# board1corrected.net
KiCad netlist of a schematic drawn in EAGLE
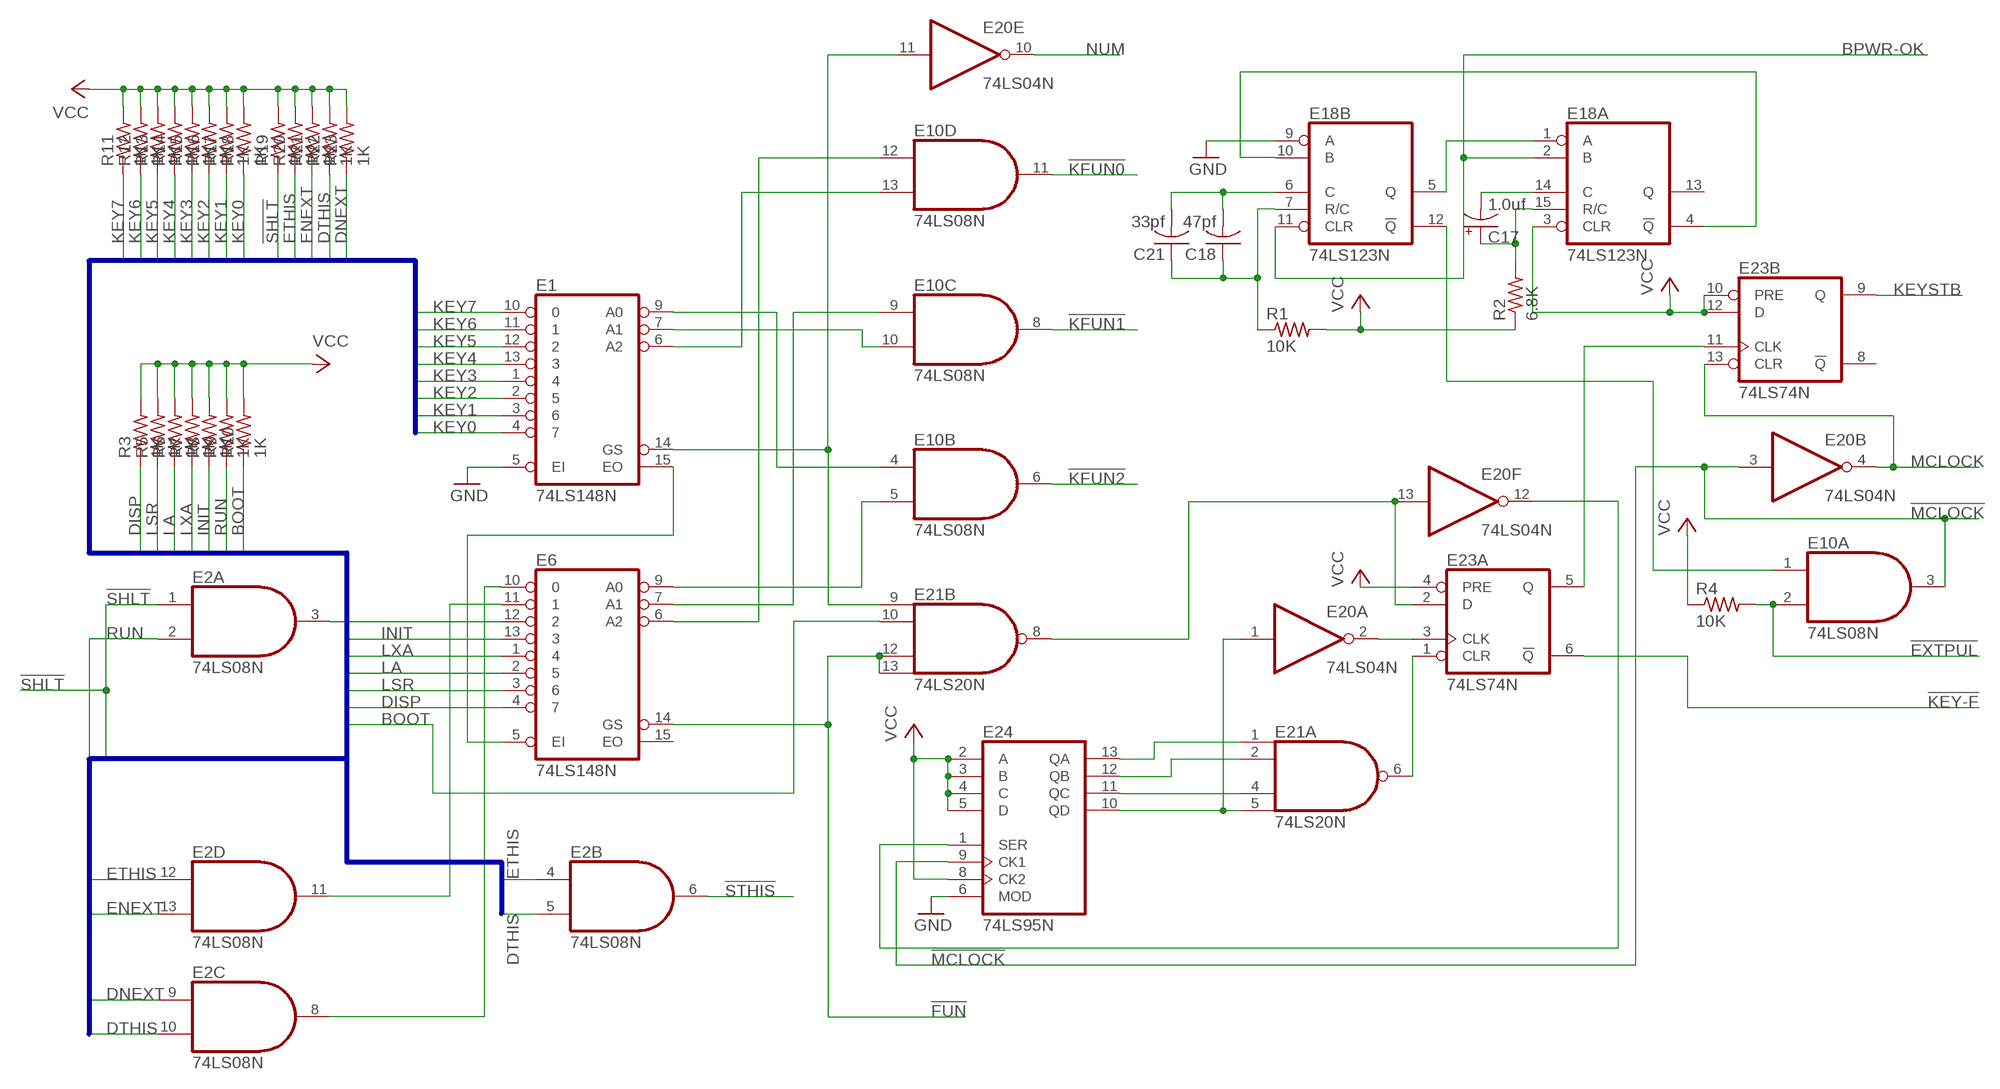
[diagram p0: schematic, sheet 1]
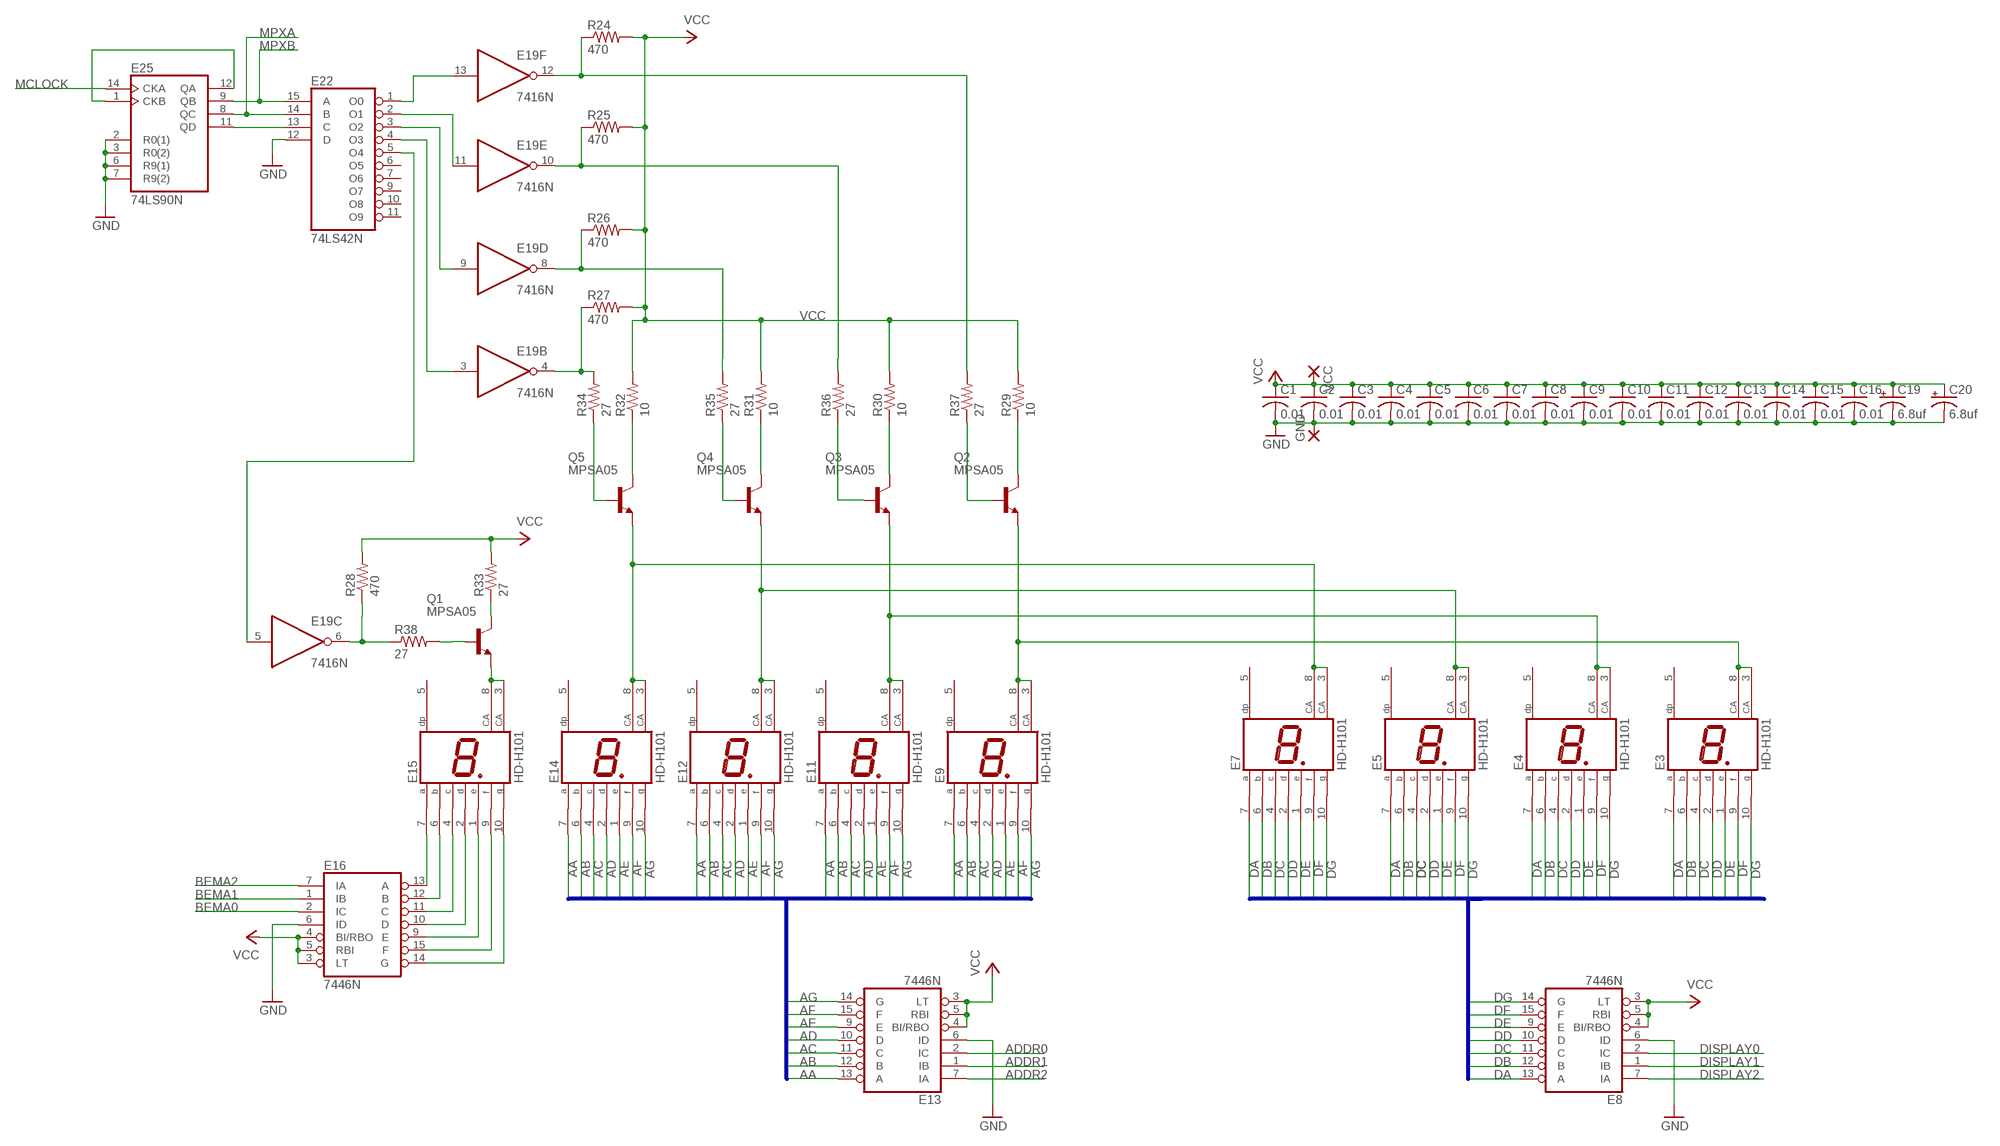
[diagram p1: schematic, sheet 2]
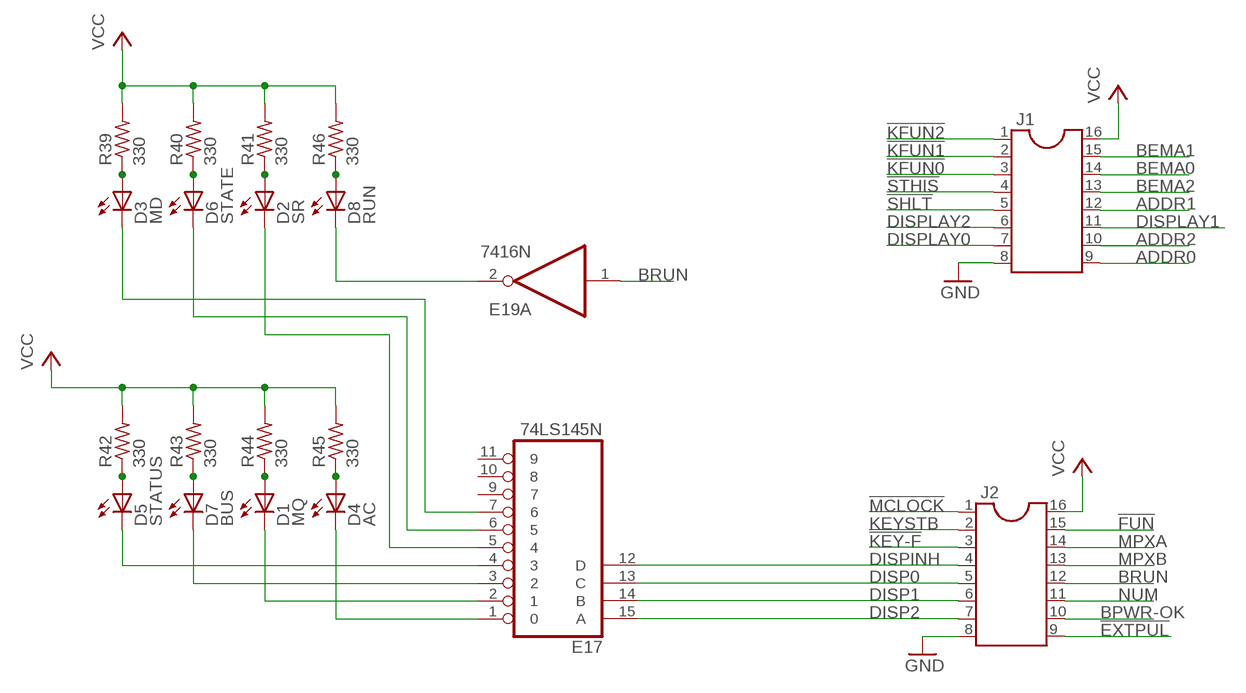
[diagram p2: schematic, sheet 3]
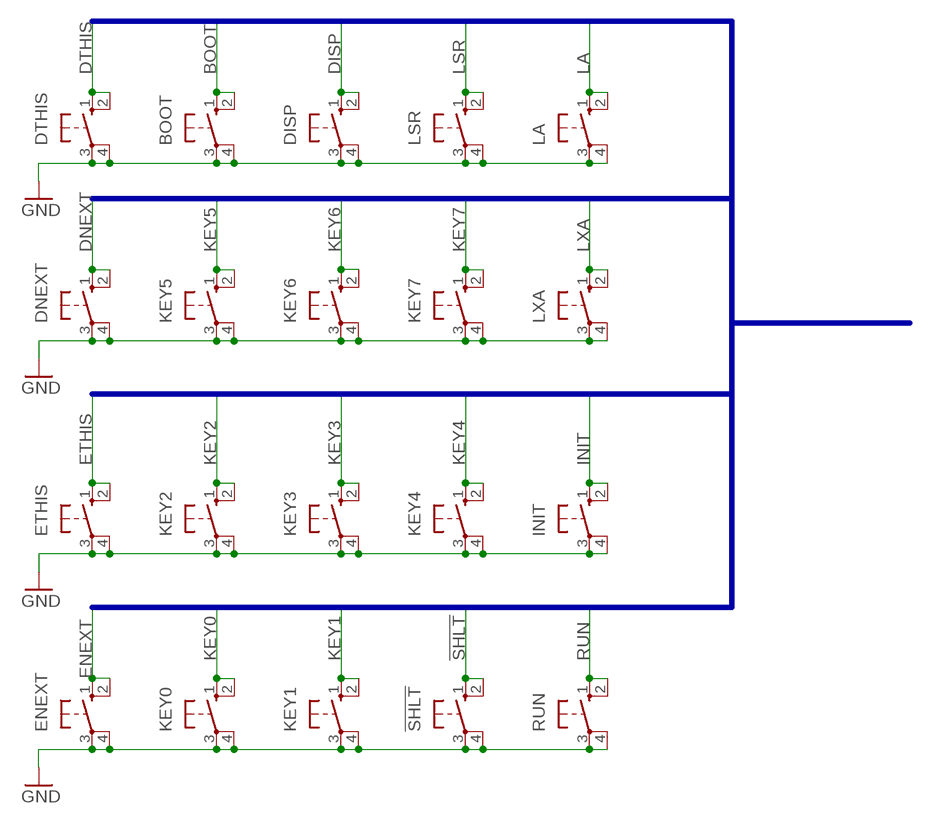
[diagram p3: schematic, sheet 4]

(export (version "E")
  (design (tool "Eeschema 10.0.6"))
  (components
    (comp (ref "C1")
      (value "0.01")
      (footprint "eagle-import:C050-025X075")
      (libsource (lib "eagle-import") (part "C-US050-025X075"))
    )
    (comp (ref "C2")
      (value "0.01")
      (footprint "eagle-import:C050-025X075")
      (libsource (lib "eagle-import") (part "C-US050-025X075"))
    )
    (comp (ref "C3")
      (value "0.01")
      (footprint "eagle-import:C050-025X075")
      (libsource (lib "eagle-import") (part "C-US050-025X075"))
    )
    (comp (ref "C4")
      (value "0.01")
      (footprint "eagle-import:C050-025X075")
      (libsource (lib "eagle-import") (part "C-US050-025X075"))
    )
    (comp (ref "C5")
      (value "0.01")
      (footprint "eagle-import:C050-025X075")
      (libsource (lib "eagle-import") (part "C-US050-025X075"))
    )
    (comp (ref "C6")
      (value "0.01")
      (footprint "eagle-import:C050-025X075")
      (libsource (lib "eagle-import") (part "C-US050-025X075"))
    )
    (comp (ref "C7")
      (value "0.01")
      (footprint "eagle-import:C050-025X075")
      (libsource (lib "eagle-import") (part "C-US050-025X075"))
    )
    (comp (ref "C8")
      (value "0.01")
      (footprint "eagle-import:C050-025X075")
      (libsource (lib "eagle-import") (part "C-US050-025X075"))
    )
    (comp (ref "C9")
      (value "0.01")
      (footprint "eagle-import:C050-025X075")
      (libsource (lib "eagle-import") (part "C-US050-025X075"))
    )
    (comp (ref "C10")
      (value "0.01")
      (footprint "eagle-import:C050-025X075")
      (libsource (lib "eagle-import") (part "C-US050-025X075"))
    )
    (comp (ref "C11")
      (value "0.01")
      (footprint "eagle-import:C050-025X075")
      (libsource (lib "eagle-import") (part "C-US050-025X075"))
    )
    (comp (ref "C12")
      (value "0.01")
      (footprint "eagle-import:C050-025X075")
      (libsource (lib "eagle-import") (part "C-US050-025X075"))
    )
    (comp (ref "C13")
      (value "0.01")
      (footprint "eagle-import:C050-025X075")
      (libsource (lib "eagle-import") (part "C-US050-025X075"))
    )
    (comp (ref "C14")
      (value "0.01")
      (footprint "eagle-import:C050-025X075")
      (libsource (lib "eagle-import") (part "C-US050-025X075"))
    )
    (comp (ref "C15")
      (value "0.01")
      (footprint "eagle-import:C050-025X075")
      (libsource (lib "eagle-import") (part "C-US050-025X075"))
    )
    (comp (ref "C16")
      (value "0.01")
      (footprint "eagle-import:C050-025X075")
      (libsource (lib "eagle-import") (part "C-US050-025X075"))
    )
    (comp (ref "C19")
      (value "6.8uf")
      (footprint "eagle-import:E22-6")
      (libsource (lib "eagle-import") (part "CPOL-USE22-6AXIAL"))
    )
    (comp (ref "C20")
      (value "6.8uf")
      (footprint "eagle-import:E22-6")
      (libsource (lib "eagle-import") (part "CPOL-USE22-6AXIAL"))
    )
    (comp (ref "E3")
      (value "HD-H101")
      (footprint "eagle-import:HDSP-M")
      (libsource (lib "eagle-import") (part "HD-H101"))
    )
    (comp (ref "E4")
      (value "HD-H101")
      (footprint "eagle-import:HDSP-M")
      (libsource (lib "eagle-import") (part "HD-H101"))
    )
    (comp (ref "E5")
      (value "HD-H101")
      (footprint "eagle-import:HDSP-M")
      (libsource (lib "eagle-import") (part "HD-H101"))
    )
    (comp (ref "E7")
      (value "HD-H101")
      (footprint "eagle-import:HDSP-M")
      (libsource (lib "eagle-import") (part "HD-H101"))
    )
    (comp (ref "E8")
      (value "7446N")
      (footprint "eagle-import:DIL16")
      (libsource (lib "eagle-import") (part "7446N"))
    )
    (comp (ref "E9")
      (value "HD-H101")
      (footprint "eagle-import:HDSP-M")
      (libsource (lib "eagle-import") (part "HD-H101"))
    )
    (comp (ref "E11")
      (value "HD-H101")
      (footprint "eagle-import:HDSP-M")
      (libsource (lib "eagle-import") (part "HD-H101"))
    )
    (comp (ref "E12")
      (value "HD-H101")
      (footprint "eagle-import:HDSP-M")
      (libsource (lib "eagle-import") (part "HD-H101"))
    )
    (comp (ref "E13")
      (value "7446N")
      (footprint "eagle-import:DIL16")
      (libsource (lib "eagle-import") (part "7446N"))
    )
    (comp (ref "E14")
      (value "HD-H101")
      (footprint "eagle-import:HDSP-M")
      (libsource (lib "eagle-import") (part "HD-H101"))
    )
    (comp (ref "E15")
      (value "HD-H101")
      (footprint "eagle-import:HDSP-M")
      (libsource (lib "eagle-import") (part "HD-H101"))
    )
    (comp (ref "E16")
      (value "7446N")
      (footprint "eagle-import:DIL16")
      (libsource (lib "eagle-import") (part "7446N"))
    )
    (comp (ref "E19")
      (value "7416N")
      (footprint "eagle-import:DIL14")
      (libsource (lib "eagle-import") (part "7416N"))
    )
    (comp (ref "E22")
      (value "74LS42N")
      (footprint "eagle-import:DIL16")
      (libsource (lib "eagle-import") (part "7442NLS"))
    )
    (comp (ref "E25")
      (value "74LS90N")
      (footprint "eagle-import:DIL14")
      (libsource (lib "eagle-import") (part "7490NLS"))
    )
    (comp (ref "GND")
      (value "3,81/1,4")
      (footprint "eagle-import:3,81_1,4")
      (libsource (lib "eagle-import") (part "3,81/1,4"))
    )
    (comp (ref "Q1")
      (value "MPSA05")
      (footprint "eagle-import:TO18")
      (libsource (lib "eagle-import") (part "2N2222A"))
    )
    (comp (ref "Q2")
      (value "MPSA05")
      (footprint "eagle-import:TO18")
      (libsource (lib "eagle-import") (part "2N2222A"))
    )
    (comp (ref "Q3")
      (value "MPSA05")
      (footprint "eagle-import:TO18")
      (libsource (lib "eagle-import") (part "2N2222A"))
    )
    (comp (ref "Q4")
      (value "MPSA05")
      (footprint "eagle-import:TO18")
      (libsource (lib "eagle-import") (part "2N2222A"))
    )
    (comp (ref "Q5")
      (value "MPSA05")
      (footprint "eagle-import:TO18")
      (libsource (lib "eagle-import") (part "2N2222A"))
    )
    (comp (ref "R24")
      (value "470")
      (footprint "eagle-import:0207_10")
      (libsource (lib "eagle-import") (part "R-US_0207/10"))
    )
    (comp (ref "R25")
      (value "470")
      (footprint "eagle-import:0207_10")
      (libsource (lib "eagle-import") (part "R-US_0207/10"))
    )
    (comp (ref "R26")
      (value "470")
      (footprint "eagle-import:0207_10")
      (libsource (lib "eagle-import") (part "R-US_0207/10"))
    )
    (comp (ref "R27")
      (value "470")
      (footprint "eagle-import:0207_10")
      (libsource (lib "eagle-import") (part "R-US_0207/10"))
    )
    (comp (ref "R28")
      (value "470")
      (footprint "eagle-import:0207_10")
      (libsource (lib "eagle-import") (part "R-US_0207/10"))
    )
    (comp (ref "R29")
      (value "10")
      (footprint "eagle-import:0207_10")
      (libsource (lib "eagle-import") (part "R-US_0207/10"))
    )
    (comp (ref "R30")
      (value "10")
      (footprint "eagle-import:0207_10")
      (libsource (lib "eagle-import") (part "R-US_0207/10"))
    )
    (comp (ref "R31")
      (value "10")
      (footprint "eagle-import:0207_10")
      (libsource (lib "eagle-import") (part "R-US_0207/10"))
    )
    (comp (ref "R32")
      (value "10")
      (footprint "eagle-import:0207_10")
      (libsource (lib "eagle-import") (part "R-US_0207/10"))
    )
    (comp (ref "R33")
      (value "27")
      (footprint "eagle-import:0207_10")
      (libsource (lib "eagle-import") (part "R-US_0207/10"))
    )
    (comp (ref "R34")
      (value "27")
      (footprint "eagle-import:0207_10")
      (libsource (lib "eagle-import") (part "R-US_0207/10"))
    )
    (comp (ref "R35")
      (value "27")
      (footprint "eagle-import:0207_10")
      (libsource (lib "eagle-import") (part "R-US_0207/10"))
    )
    (comp (ref "R36")
      (value "27")
      (footprint "eagle-import:0207_10")
      (libsource (lib "eagle-import") (part "R-US_0207/10"))
    )
    (comp (ref "R37")
      (value "27")
      (footprint "eagle-import:0207_10")
      (libsource (lib "eagle-import") (part "R-US_0207/10"))
    )
    (comp (ref "R38")
      (value "27")
      (footprint "eagle-import:0207_10")
      (libsource (lib "eagle-import") (part "R-US_0207/10"))
    )
    (comp (ref "VCC")
      (value "3,81/1,4")
      (footprint "eagle-import:3,81_1,4")
      (libsource (lib "eagle-import") (part "3,81/1,4"))
    )
    (comp (ref "C17")
      (value "1.0uf")
      (footprint "eagle-import:E15-5")
      (libsource (lib "eagle-import") (part "CPOL-USE15-5AXIAL"))
    )
    (comp (ref "C18")
      (value "47pf")
      (footprint "eagle-import:C050-025X075")
      (libsource (lib "eagle-import") (part "C-US050-025X075"))
    )
    (comp (ref "C21")
      (value "33pf")
      (footprint "eagle-import:C050-025X075")
      (libsource (lib "eagle-import") (part "C-US050-025X075"))
    )
    (comp (ref "E1")
      (value "74LS148N")
      (footprint "eagle-import:DIL16")
      (libsource (lib "eagle-import") (part "74148NLS"))
    )
    (comp (ref "E2")
      (value "74LS08N")
      (footprint "eagle-import:DIL14")
      (libsource (lib "eagle-import") (part "7408NLS"))
    )
    (comp (ref "E6")
      (value "74LS148N")
      (footprint "eagle-import:DIL16")
      (libsource (lib "eagle-import") (part "74148NLS"))
    )
    (comp (ref "E10")
      (value "74LS08N")
      (footprint "eagle-import:DIL14")
      (libsource (lib "eagle-import") (part "7408NLS"))
    )
    (comp (ref "E18")
      (value "74LS123N")
      (footprint "eagle-import:DIL16")
      (libsource (lib "eagle-import") (part "74123NLS"))
    )
    (comp (ref "E20")
      (value "74LS04N")
      (footprint "eagle-import:DIL14")
      (libsource (lib "eagle-import") (part "7404NLS"))
    )
    (comp (ref "E21")
      (value "74LS20N")
      (footprint "eagle-import:DIL14")
      (libsource (lib "eagle-import") (part "7420NLS"))
    )
    (comp (ref "E23")
      (value "74LS74N")
      (footprint "eagle-import:DIL14")
      (libsource (lib "eagle-import") (part "7474NLS"))
    )
    (comp (ref "E24")
      (value "74LS95N")
      (footprint "eagle-import:DIL14")
      (libsource (lib "eagle-import") (part "7495NLS"))
    )
    (comp (ref "R1")
      (value "10K")
      (footprint "eagle-import:0207_10")
      (libsource (lib "eagle-import") (part "R-US_0207/10"))
    )
    (comp (ref "R2")
      (value "6.8K")
      (footprint "eagle-import:0207_10")
      (libsource (lib "eagle-import") (part "R-US_0207/10"))
    )
    (comp (ref "R3")
      (value "1K")
      (footprint "eagle-import:0207_10")
      (libsource (lib "eagle-import") (part "R-US_0207/10"))
    )
    (comp (ref "R4")
      (value "10K")
      (footprint "eagle-import:0207_10")
      (libsource (lib "eagle-import") (part "R-US_0207/10"))
    )
    (comp (ref "R5")
      (value "1K")
      (footprint "eagle-import:0207_10")
      (libsource (lib "eagle-import") (part "R-US_0207/10"))
    )
    (comp (ref "R6")
      (value "1K")
      (footprint "eagle-import:0207_10")
      (libsource (lib "eagle-import") (part "R-US_0207/10"))
    )
    (comp (ref "R7")
      (value "1K")
      (footprint "eagle-import:0207_10")
      (libsource (lib "eagle-import") (part "R-US_0207/10"))
    )
    (comp (ref "R8")
      (value "1K")
      (footprint "eagle-import:0207_10")
      (libsource (lib "eagle-import") (part "R-US_0207/10"))
    )
    (comp (ref "R9")
      (value "1K")
      (footprint "eagle-import:0207_10")
      (libsource (lib "eagle-import") (part "R-US_0207/10"))
    )
    (comp (ref "R10")
      (value "1K")
      (footprint "eagle-import:0207_10")
      (libsource (lib "eagle-import") (part "R-US_0207/10"))
    )
    (comp (ref "R11")
      (value "1K")
      (footprint "eagle-import:0207_10")
      (libsource (lib "eagle-import") (part "R-US_0207/10"))
    )
    (comp (ref "R12")
      (value "1K")
      (footprint "eagle-import:0207_10")
      (libsource (lib "eagle-import") (part "R-US_0207/10"))
    )
    (comp (ref "R13")
      (value "1K")
      (footprint "eagle-import:0207_10")
      (libsource (lib "eagle-import") (part "R-US_0207/10"))
    )
    (comp (ref "R14")
      (value "1K")
      (footprint "eagle-import:0207_10")
      (libsource (lib "eagle-import") (part "R-US_0207/10"))
    )
    (comp (ref "R15")
      (value "1K")
      (footprint "eagle-import:0207_10")
      (libsource (lib "eagle-import") (part "R-US_0207/10"))
    )
    (comp (ref "R16")
      (value "1K")
      (footprint "eagle-import:0207_10")
      (libsource (lib "eagle-import") (part "R-US_0207/10"))
    )
    (comp (ref "R17")
      (value "1K")
      (footprint "eagle-import:0207_10")
      (libsource (lib "eagle-import") (part "R-US_0207/10"))
    )
    (comp (ref "R18")
      (value "1K")
      (footprint "eagle-import:0207_10")
      (libsource (lib "eagle-import") (part "R-US_0207/10"))
    )
    (comp (ref "R19")
      (value "1K")
      (footprint "eagle-import:0207_10")
      (libsource (lib "eagle-import") (part "R-US_0207/10"))
    )
    (comp (ref "R20")
      (value "1K")
      (footprint "eagle-import:0207_10")
      (libsource (lib "eagle-import") (part "R-US_0207/10"))
    )
    (comp (ref "R21")
      (value "1K")
      (footprint "eagle-import:0207_10")
      (libsource (lib "eagle-import") (part "R-US_0207/10"))
    )
    (comp (ref "R22")
      (value "1K")
      (footprint "eagle-import:0207_10")
      (libsource (lib "eagle-import") (part "R-US_0207/10"))
    )
    (comp (ref "R23")
      (value "1K")
      (footprint "eagle-import:0207_10")
      (libsource (lib "eagle-import") (part "R-US_0207/10"))
    )
    (comp (ref "D1")
      (value "MQ")
      (footprint "eagle-import:LED5MM")
      (libsource (lib "eagle-import") (part "LED5MM"))
    )
    (comp (ref "D2")
      (value "SR")
      (footprint "eagle-import:LED5MM")
      (libsource (lib "eagle-import") (part "LED5MM"))
    )
    (comp (ref "D3")
      (value "MD")
      (footprint "eagle-import:LED5MM")
      (libsource (lib "eagle-import") (part "LED5MM"))
    )
    (comp (ref "D4")
      (value "AC")
      (footprint "eagle-import:LED5MM")
      (libsource (lib "eagle-import") (part "LED5MM"))
    )
    (comp (ref "D5")
      (value "STATUS")
      (footprint "eagle-import:LED5MM")
      (libsource (lib "eagle-import") (part "LED5MM"))
    )
    (comp (ref "D6")
      (value "STATE")
      (footprint "eagle-import:LED5MM")
      (libsource (lib "eagle-import") (part "LED5MM"))
    )
    (comp (ref "D7")
      (value "BUS")
      (footprint "eagle-import:LED5MM")
      (libsource (lib "eagle-import") (part "LED5MM"))
    )
    (comp (ref "D8")
      (value "RUN")
      (footprint "eagle-import:LED5MM")
      (libsource (lib "eagle-import") (part "LED5MM"))
    )
    (comp (ref "E17")
      (value "74LS145N")
      (footprint "eagle-import:DIL16")
      (libsource (lib "eagle-import") (part "74145NLS"))
    )
    (comp (ref "J1")
      (value "DIL16S")
      (footprint "eagle-import:SOCKET-16")
      (libsource (lib "eagle-import") (part "DIL16S"))
    )
    (comp (ref "J2")
      (value "DIL16S")
      (footprint "eagle-import:SOCKET-16")
      (libsource (lib "eagle-import") (part "DIL16S"))
    )
    (comp (ref "R39")
      (value "330")
      (footprint "eagle-import:0207_10")
      (libsource (lib "eagle-import") (part "R-US_0207/10"))
    )
    (comp (ref "R40")
      (value "330")
      (footprint "eagle-import:0207_10")
      (libsource (lib "eagle-import") (part "R-US_0207/10"))
    )
    (comp (ref "R41")
      (value "330")
      (footprint "eagle-import:0207_10")
      (libsource (lib "eagle-import") (part "R-US_0207/10"))
    )
    (comp (ref "R42")
      (value "330")
      (footprint "eagle-import:0207_10")
      (libsource (lib "eagle-import") (part "R-US_0207/10"))
    )
    (comp (ref "R43")
      (value "330")
      (footprint "eagle-import:0207_10")
      (libsource (lib "eagle-import") (part "R-US_0207/10"))
    )
    (comp (ref "R44")
      (value "330")
      (footprint "eagle-import:0207_10")
      (libsource (lib "eagle-import") (part "R-US_0207/10"))
    )
    (comp (ref "R45")
      (value "330")
      (footprint "eagle-import:0207_10")
      (libsource (lib "eagle-import") (part "R-US_0207/10"))
    )
    (comp (ref "R46")
      (value "330")
      (footprint "eagle-import:0207_10")
      (libsource (lib "eagle-import") (part "R-US_0207/10"))
    )
    (comp (ref "!SHLT")
      (value "40-XX")
      (footprint "eagle-import:B3F-40XX")
      (fields (field (name "MF") "OMRON COMPONENTS USA") (field (name "MPN") "B3F-4000"))
      (libsource (lib "eagle-import") (part "40-XX"))
    )
    (comp (ref "BOOT")
      (value "40-XX")
      (footprint "eagle-import:B3F-40XX")
      (fields (field (name "MF") "OMRON COMPONENTS USA") (field (name "MPN") "B3F-4000"))
      (libsource (lib "eagle-import") (part "40-XX"))
    )
    (comp (ref "DISP")
      (value "40-XX")
      (footprint "eagle-import:B3F-40XX")
      (fields (field (name "MF") "OMRON COMPONENTS USA") (field (name "MPN") "B3F-4000"))
      (libsource (lib "eagle-import") (part "40-XX"))
    )
    (comp (ref "DNEXT")
      (value "40-XX")
      (footprint "eagle-import:B3F-40XX")
      (fields (field (name "MF") "OMRON COMPONENTS USA") (field (name "MPN") "B3F-4000"))
      (libsource (lib "eagle-import") (part "40-XX"))
    )
    (comp (ref "DTHIS")
      (value "40-XX")
      (footprint "eagle-import:B3F-40XX")
      (fields (field (name "MF") "OMRON COMPONENTS USA") (field (name "MPN") "B3F-4000"))
      (libsource (lib "eagle-import") (part "40-XX"))
    )
    (comp (ref "ENEXT")
      (value "40-XX")
      (footprint "eagle-import:B3F-40XX")
      (fields (field (name "MF") "OMRON COMPONENTS USA") (field (name "MPN") "B3F-4000"))
      (libsource (lib "eagle-import") (part "40-XX"))
    )
    (comp (ref "ETHIS")
      (value "40-XX")
      (footprint "eagle-import:B3F-40XX")
      (fields (field (name "MF") "OMRON COMPONENTS USA") (field (name "MPN") "B3F-4000"))
      (libsource (lib "eagle-import") (part "40-XX"))
    )
    (comp (ref "INIT")
      (value "40-XX")
      (footprint "eagle-import:B3F-40XX")
      (fields (field (name "MF") "OMRON COMPONENTS USA") (field (name "MPN") "B3F-4000"))
      (libsource (lib "eagle-import") (part "40-XX"))
    )
    (comp (ref "KEY0")
      (value "40-XX")
      (footprint "eagle-import:B3F-40XX")
      (fields (field (name "MF") "OMRON COMPONENTS USA") (field (name "MPN") "B3F-4000"))
      (libsource (lib "eagle-import") (part "40-XX"))
    )
    (comp (ref "KEY1")
      (value "40-XX")
      (footprint "eagle-import:B3F-40XX")
      (fields (field (name "MF") "OMRON COMPONENTS USA") (field (name "MPN") "B3F-4000"))
      (libsource (lib "eagle-import") (part "40-XX"))
    )
    (comp (ref "KEY2")
      (value "40-XX")
      (footprint "eagle-import:B3F-40XX")
      (fields (field (name "MF") "OMRON COMPONENTS USA") (field (name "MPN") "B3F-4000"))
      (libsource (lib "eagle-import") (part "40-XX"))
    )
    (comp (ref "KEY3")
      (value "40-XX")
      (footprint "eagle-import:B3F-40XX")
      (fields (field (name "MF") "OMRON COMPONENTS USA") (field (name "MPN") "B3F-4000"))
      (libsource (lib "eagle-import") (part "40-XX"))
    )
    (comp (ref "KEY4")
      (value "40-XX")
      (footprint "eagle-import:B3F-40XX")
      (fields (field (name "MF") "OMRON COMPONENTS USA") (field (name "MPN") "B3F-4000"))
      (libsource (lib "eagle-import") (part "40-XX"))
    )
    (comp (ref "KEY5")
      (value "40-XX")
      (footprint "eagle-import:B3F-40XX")
      (fields (field (name "MF") "OMRON COMPONENTS USA") (field (name "MPN") "B3F-4000"))
      (libsource (lib "eagle-import") (part "40-XX"))
    )
    (comp (ref "KEY6")
      (value "40-XX")
      (footprint "eagle-import:B3F-40XX")
      (fields (field (name "MF") "OMRON COMPONENTS USA") (field (name "MPN") "B3F-4000"))
      (libsource (lib "eagle-import") (part "40-XX"))
    )
    (comp (ref "KEY7")
      (value "40-XX")
      (footprint "eagle-import:B3F-40XX")
      (fields (field (name "MF") "OMRON COMPONENTS USA") (field (name "MPN") "B3F-4000"))
      (libsource (lib "eagle-import") (part "40-XX"))
    )
    (comp (ref "LA")
      (value "40-XX")
      (footprint "eagle-import:B3F-40XX")
      (fields (field (name "MF") "OMRON COMPONENTS USA") (field (name "MPN") "B3F-4000"))
      (libsource (lib "eagle-import") (part "40-XX"))
    )
    (comp (ref "LSR")
      (value "40-XX")
      (footprint "eagle-import:B3F-40XX")
      (fields (field (name "MF") "OMRON COMPONENTS USA") (field (name "MPN") "B3F-4000"))
      (libsource (lib "eagle-import") (part "40-XX"))
    )
    (comp (ref "LXA")
      (value "40-XX")
      (footprint "eagle-import:B3F-40XX")
      (fields (field (name "MF") "OMRON COMPONENTS USA") (field (name "MPN") "B3F-4000"))
      (libsource (lib "eagle-import") (part "40-XX"))
    )
    (comp (ref "RUN")
      (value "40-XX")
      (footprint "eagle-import:B3F-40XX")
      (fields (field (name "MF") "OMRON COMPONENTS USA") (field (name "MPN") "B3F-4000"))
      (libsource (lib "eagle-import") (part "40-XX"))
    )
  )
  (nets
    (net (code "1") (name "AA") (class "Default")
      (node (ref "E11") (pin "7") (pinfunction "A_7") (pintype "passive"))
      (node (ref "E12") (pin "7") (pinfunction "A_7") (pintype "passive"))
      (node (ref "E13") (pin "13") (pinfunction "A_13") (pintype "open_collector"))
      (node (ref "E14") (pin "7") (pinfunction "A_7") (pintype "passive"))
      (node (ref "E9") (pin "7") (pinfunction "A_7") (pintype "passive"))
    )
    (net (code "2") (name "AB") (class "Default")
      (node (ref "E11") (pin "6") (pinfunction "B_6") (pintype "passive"))
      (node (ref "E12") (pin "6") (pinfunction "B_6") (pintype "passive"))
      (node (ref "E13") (pin "12") (pinfunction "B_12") (pintype "open_collector"))
      (node (ref "E14") (pin "6") (pinfunction "B_6") (pintype "passive"))
      (node (ref "E9") (pin "6") (pinfunction "B_6") (pintype "passive"))
    )
    (net (code "3") (name "AC") (class "Default")
      (node (ref "E11") (pin "4") (pinfunction "C_4") (pintype "passive"))
      (node (ref "E12") (pin "4") (pinfunction "C_4") (pintype "passive"))
      (node (ref "E13") (pin "11") (pinfunction "C_11") (pintype "open_collector"))
      (node (ref "E14") (pin "4") (pinfunction "C_4") (pintype "passive"))
      (node (ref "E9") (pin "4") (pinfunction "C_4") (pintype "passive"))
    )
    (net (code "4") (name "AD") (class "Default")
      (node (ref "E11") (pin "2") (pinfunction "D_2") (pintype "passive"))
      (node (ref "E12") (pin "2") (pinfunction "D_2") (pintype "passive"))
      (node (ref "E13") (pin "10") (pinfunction "D_10") (pintype "open_collector"))
      (node (ref "E14") (pin "2") (pinfunction "D_2") (pintype "passive"))
      (node (ref "E9") (pin "2") (pinfunction "D_2") (pintype "passive"))
    )
    (net (code "5") (name "ADDR0") (class "Default")
      (node (ref "E13") (pin "2") (pinfunction "IC_2") (pintype "input"))
      (node (ref "J1") (pin "9") (pinfunction "9_9") (pintype "passive"))
    )
    (net (code "6") (name "ADDR1") (class "Default")
      (node (ref "E13") (pin "1") (pinfunction "IB_1") (pintype "input"))
      (node (ref "J1") (pin "12") (pinfunction "12_12") (pintype "passive"))
    )
    (net (code "7") (name "ADDR2") (class "Default")
      (node (ref "E13") (pin "7") (pinfunction "IA_7") (pintype "input"))
      (node (ref "J1") (pin "10") (pinfunction "10_10") (pintype "passive"))
    )
    (net (code "8") (name "AE") (class "Default")
      (node (ref "E11") (pin "1") (pinfunction "E_1") (pintype "passive"))
      (node (ref "E12") (pin "1") (pinfunction "E_1") (pintype "passive"))
      (node (ref "E13") (pin "9") (pinfunction "E_9") (pintype "open_collector"))
      (node (ref "E14") (pin "1") (pinfunction "E_1") (pintype "passive"))
      (node (ref "E9") (pin "1") (pinfunction "E_1") (pintype "passive"))
    )
    (net (code "9") (name "AF") (class "Default")
      (node (ref "E11") (pin "9") (pinfunction "F_9") (pintype "passive"))
      (node (ref "E12") (pin "9") (pinfunction "F_9") (pintype "passive"))
      (node (ref "E13") (pin "15") (pinfunction "F_15") (pintype "open_collector"))
      (node (ref "E14") (pin "9") (pinfunction "F_9") (pintype "passive"))
      (node (ref "E9") (pin "9") (pinfunction "F_9") (pintype "passive"))
    )
    (net (code "10") (name "AG") (class "Default")
      (node (ref "E11") (pin "10") (pinfunction "G_10") (pintype "passive"))
      (node (ref "E12") (pin "10") (pinfunction "G_10") (pintype "passive"))
      (node (ref "E13") (pin "14") (pinfunction "G_14") (pintype "open_collector"))
      (node (ref "E14") (pin "10") (pinfunction "G_10") (pintype "passive"))
      (node (ref "E9") (pin "10") (pinfunction "G_10") (pintype "passive"))
    )
    (net (code "11") (name "BEMA0") (class "Default")
      (node (ref "E16") (pin "2") (pinfunction "IC_2") (pintype "input"))
      (node (ref "J1") (pin "14") (pinfunction "14_14") (pintype "passive"))
    )
    (net (code "12") (name "BEMA1") (class "Default")
      (node (ref "E16") (pin "1") (pinfunction "IB_1") (pintype "input"))
      (node (ref "J1") (pin "15") (pinfunction "15_15") (pintype "passive"))
    )
    (net (code "13") (name "BEMA2") (class "Default")
      (node (ref "E16") (pin "7") (pinfunction "IA_7") (pintype "input"))
      (node (ref "J1") (pin "13") (pinfunction "13_13") (pintype "passive"))
    )
    (net (code "14") (name "BOOT") (class "Default")
      (node (ref "BOOT") (pin "1") (pinfunction "S_1") (pintype "passive"))
      (node (ref "BOOT") (pin "2") (pinfunction "S1_2") (pintype "passive"))
      (node (ref "E21") (pin "10") (pinfunction "I1_10") (pintype "input"))
      (node (ref "R10") (pin "1") (pinfunction "1_1") (pintype "passive"))
    )
    (net (code "15") (name "BPWR-OK") (class "Default")
      (node (ref "E18") (pin "11") (pinfunction "CLR_11") (pintype "input"))
      (node (ref "E18") (pin "2") (pinfunction "B_2") (pintype "input"))
      (node (ref "J2") (pin "10") (pinfunction "10_10") (pintype "passive"))
    )
    (net (code "16") (name "BRUN") (class "Default")
      (node (ref "E19") (pin "1") (pinfunction "I_1") (pintype "input"))
      (node (ref "J2") (pin "12") (pinfunction "12_12") (pintype "passive"))
    )
    (net (code "17") (name "DA") (class "Default")
      (node (ref "E3") (pin "7") (pinfunction "A_7") (pintype "passive"))
      (node (ref "E4") (pin "7") (pinfunction "A_7") (pintype "passive"))
      (node (ref "E5") (pin "7") (pinfunction "A_7") (pintype "passive"))
      (node (ref "E7") (pin "7") (pinfunction "A_7") (pintype "passive"))
      (node (ref "E8") (pin "13") (pinfunction "A_13") (pintype "open_collector"))
    )
    (net (code "18") (name "DB") (class "Default")
      (node (ref "E3") (pin "6") (pinfunction "B_6") (pintype "passive"))
      (node (ref "E4") (pin "6") (pinfunction "B_6") (pintype "passive"))
      (node (ref "E5") (pin "6") (pinfunction "B_6") (pintype "passive"))
      (node (ref "E7") (pin "6") (pinfunction "B_6") (pintype "passive"))
      (node (ref "E8") (pin "12") (pinfunction "B_12") (pintype "open_collector"))
    )
    (net (code "19") (name "DC") (class "Default")
      (node (ref "E3") (pin "4") (pinfunction "C_4") (pintype "passive"))
      (node (ref "E4") (pin "4") (pinfunction "C_4") (pintype "passive"))
      (node (ref "E5") (pin "4") (pinfunction "C_4") (pintype "passive"))
      (node (ref "E7") (pin "4") (pinfunction "C_4") (pintype "passive"))
      (node (ref "E8") (pin "11") (pinfunction "C_11") (pintype "open_collector"))
    )
    (net (code "20") (name "DD") (class "Default")
      (node (ref "E3") (pin "2") (pinfunction "D_2") (pintype "passive"))
      (node (ref "E4") (pin "2") (pinfunction "D_2") (pintype "passive"))
      (node (ref "E5") (pin "2") (pinfunction "D_2") (pintype "passive"))
      (node (ref "E7") (pin "2") (pinfunction "D_2") (pintype "passive"))
      (node (ref "E8") (pin "10") (pinfunction "D_10") (pintype "open_collector"))
    )
    (net (code "21") (name "DE") (class "Default")
      (node (ref "E3") (pin "1") (pinfunction "E_1") (pintype "passive"))
      (node (ref "E4") (pin "1") (pinfunction "E_1") (pintype "passive"))
      (node (ref "E5") (pin "1") (pinfunction "E_1") (pintype "passive"))
      (node (ref "E7") (pin "1") (pinfunction "E_1") (pintype "passive"))
      (node (ref "E8") (pin "9") (pinfunction "E_9") (pintype "open_collector"))
    )
    (net (code "22") (name "DF") (class "Default")
      (node (ref "E3") (pin "9") (pinfunction "F_9") (pintype "passive"))
      (node (ref "E4") (pin "9") (pinfunction "F_9") (pintype "passive"))
      (node (ref "E5") (pin "9") (pinfunction "F_9") (pintype "passive"))
      (node (ref "E7") (pin "9") (pinfunction "F_9") (pintype "passive"))
      (node (ref "E8") (pin "15") (pinfunction "F_15") (pintype "open_collector"))
    )
    (net (code "23") (name "DG") (class "Default")
      (node (ref "E3") (pin "10") (pinfunction "G_10") (pintype "passive"))
      (node (ref "E4") (pin "10") (pinfunction "G_10") (pintype "passive"))
      (node (ref "E5") (pin "10") (pinfunction "G_10") (pintype "passive"))
      (node (ref "E7") (pin "10") (pinfunction "G_10") (pintype "passive"))
      (node (ref "E8") (pin "14") (pinfunction "G_14") (pintype "open_collector"))
    )
    (net (code "24") (name "DISP") (class "Default")
      (node (ref "DISP") (pin "1") (pinfunction "S_1") (pintype "passive"))
      (node (ref "DISP") (pin "2") (pinfunction "S1_2") (pintype "passive"))
      (node (ref "E6") (pin "4") (pinfunction "7_4") (pintype "input"))
      (node (ref "R3") (pin "1") (pinfunction "1_1") (pintype "passive"))
    )
    (net (code "25") (name "DISP0") (class "Default")
      (node (ref "E17") (pin "13") (pinfunction "C_13") (pintype "input"))
      (node (ref "J2") (pin "5") (pinfunction "5_5") (pintype "passive"))
    )
    (net (code "26") (name "DISP1") (class "Default")
      (node (ref "E17") (pin "14") (pinfunction "B_14") (pintype "input"))
      (node (ref "J2") (pin "6") (pinfunction "6_6") (pintype "passive"))
    )
    (net (code "27") (name "DISP2") (class "Default")
      (node (ref "E17") (pin "15") (pinfunction "A_15") (pintype "input"))
      (node (ref "J2") (pin "7") (pinfunction "7_7") (pintype "passive"))
    )
    (net (code "28") (name "DISPINH") (class "Default")
      (node (ref "E17") (pin "12") (pinfunction "D_12") (pintype "input"))
      (node (ref "J2") (pin "4") (pinfunction "4_4") (pintype "passive"))
    )
    (net (code "29") (name "DISPLAY0") (class "Default")
      (node (ref "E8") (pin "2") (pinfunction "IC_2") (pintype "input"))
      (node (ref "J1") (pin "7") (pinfunction "7_7") (pintype "passive"))
    )
    (net (code "30") (name "DISPLAY1") (class "Default")
      (node (ref "E8") (pin "1") (pinfunction "IB_1") (pintype "input"))
      (node (ref "J1") (pin "11") (pinfunction "11_11") (pintype "passive"))
    )
    (net (code "31") (name "DISPLAY2") (class "Default")
      (node (ref "E8") (pin "7") (pinfunction "IA_7") (pintype "input"))
      (node (ref "J1") (pin "6") (pinfunction "6_6") (pintype "passive"))
    )
    (net (code "32") (name "DNEXT") (class "Default")
      (node (ref "DNEXT") (pin "1") (pinfunction "S_1") (pintype "passive"))
      (node (ref "DNEXT") (pin "2") (pinfunction "S1_2") (pintype "passive"))
      (node (ref "E2") (pin "9") (pinfunction "I0_9") (pintype "input"))
      (node (ref "R23") (pin "1") (pinfunction "1_1") (pintype "passive"))
    )
    (net (code "33") (name "DTHIS") (class "Default")
      (node (ref "DTHIS") (pin "1") (pinfunction "S_1") (pintype "passive"))
      (node (ref "DTHIS") (pin "2") (pinfunction "S1_2") (pintype "passive"))
      (node (ref "E2") (pin "10") (pinfunction "I1_10") (pintype "input"))
      (node (ref "E2") (pin "5") (pinfunction "I1_5") (pintype "input"))
      (node (ref "R22") (pin "1") (pinfunction "1_1") (pintype "passive"))
    )
    (net (code "34") (name "ENEXT") (class "Default")
      (node (ref "E2") (pin "13") (pinfunction "I1_13") (pintype "input"))
      (node (ref "ENEXT") (pin "1") (pinfunction "S_1") (pintype "passive"))
      (node (ref "ENEXT") (pin "2") (pinfunction "S1_2") (pintype "passive"))
      (node (ref "R21") (pin "1") (pinfunction "1_1") (pintype "passive"))
    )
    (net (code "35") (name "ETHIS") (class "Default")
      (node (ref "E2") (pin "12") (pinfunction "I0_12") (pintype "input"))
      (node (ref "E2") (pin "4") (pinfunction "I0_4") (pintype "input"))
      (node (ref "ETHIS") (pin "1") (pinfunction "S_1") (pintype "passive"))
      (node (ref "ETHIS") (pin "2") (pinfunction "S1_2") (pintype "passive"))
      (node (ref "R20") (pin "1") (pinfunction "1_1") (pintype "passive"))
    )
    (net (code "36") (name "GND") (class "Default")
      (node (ref "!SHLT") (pin "3") (pinfunction "P_3") (pintype "passive"))
      (node (ref "!SHLT") (pin "4") (pinfunction "P1_4") (pintype "passive"))
      (node (ref "BOOT") (pin "3") (pinfunction "P_3") (pintype "passive"))
      (node (ref "BOOT") (pin "4") (pinfunction "P1_4") (pintype "passive"))
      (node (ref "C1") (pin "2") (pinfunction "2_2") (pintype "passive"))
      (node (ref "C10") (pin "2") (pinfunction "2_2") (pintype "passive"))
      (node (ref "C11") (pin "2") (pinfunction "2_2") (pintype "passive"))
      (node (ref "C12") (pin "2") (pinfunction "2_2") (pintype "passive"))
      (node (ref "C13") (pin "2") (pinfunction "2_2") (pintype "passive"))
      (node (ref "C14") (pin "2") (pinfunction "2_2") (pintype "passive"))
      (node (ref "C15") (pin "2") (pinfunction "2_2") (pintype "passive"))
      (node (ref "C16") (pin "2") (pinfunction "2_2") (pintype "passive"))
      (node (ref "C19") (pin "-") (pinfunction "-_-") (pintype "passive"))
      (node (ref "C2") (pin "2") (pinfunction "2_2") (pintype "passive"))
      (node (ref "C20") (pin "-") (pinfunction "-_-") (pintype "passive"))
      (node (ref "C3") (pin "2") (pinfunction "2_2") (pintype "passive"))
      (node (ref "C4") (pin "2") (pinfunction "2_2") (pintype "passive"))
      (node (ref "C5") (pin "2") (pinfunction "2_2") (pintype "passive"))
      (node (ref "C6") (pin "2") (pinfunction "2_2") (pintype "passive"))
      (node (ref "C7") (pin "2") (pinfunction "2_2") (pintype "passive"))
      (node (ref "C8") (pin "2") (pinfunction "2_2") (pintype "passive"))
      (node (ref "C9") (pin "2") (pinfunction "2_2") (pintype "passive"))
      (node (ref "DISP") (pin "3") (pinfunction "P_3") (pintype "passive"))
      (node (ref "DISP") (pin "4") (pinfunction "P1_4") (pintype "passive"))
      (node (ref "DNEXT") (pin "3") (pinfunction "P_3") (pintype "passive"))
      (node (ref "DNEXT") (pin "4") (pinfunction "P1_4") (pintype "passive"))
      (node (ref "DTHIS") (pin "3") (pinfunction "P_3") (pintype "passive"))
      (node (ref "DTHIS") (pin "4") (pinfunction "P1_4") (pintype "passive"))
      (node (ref "E1") (pin "5") (pinfunction "EI_5") (pintype "input"))
      (node (ref "E13") (pin "6") (pinfunction "ID_6") (pintype "input"))
      (node (ref "E16") (pin "6") (pinfunction "ID_6") (pintype "input"))
      (node (ref "E18") (pin "9") (pinfunction "A_9") (pintype "input"))
      (node (ref "E22") (pin "12") (pinfunction "D_12") (pintype "input"))
      (node (ref "E24") (pin "6") (pinfunction "MOD_6") (pintype "input"))
      (node (ref "E25") (pin "2") (pinfunction "R0(1)_2") (pintype "input"))
      (node (ref "E25") (pin "3") (pinfunction "R0(2)_3") (pintype "input"))
      (node (ref "E25") (pin "6") (pinfunction "R9(1)_6") (pintype "input"))
      (node (ref "E25") (pin "7") (pinfunction "R9(2)_7") (pintype "input"))
      (node (ref "E8") (pin "6") (pinfunction "ID_6") (pintype "input"))
      (node (ref "ENEXT") (pin "3") (pinfunction "P_3") (pintype "passive"))
      (node (ref "ENEXT") (pin "4") (pinfunction "P1_4") (pintype "passive"))
      (node (ref "ETHIS") (pin "3") (pinfunction "P_3") (pintype "passive"))
      (node (ref "ETHIS") (pin "4") (pinfunction "P1_4") (pintype "passive"))
      (node (ref "GND") (pin "1") (pinfunction "P_1") (pintype "passive"))
      (node (ref "INIT") (pin "3") (pinfunction "P_3") (pintype "passive"))
      (node (ref "INIT") (pin "4") (pinfunction "P1_4") (pintype "passive"))
      (node (ref "J1") (pin "8") (pinfunction "8_8") (pintype "passive"))
      (node (ref "J2") (pin "8") (pinfunction "8_8") (pintype "passive"))
      (node (ref "KEY0") (pin "3") (pinfunction "P_3") (pintype "passive"))
      (node (ref "KEY0") (pin "4") (pinfunction "P1_4") (pintype "passive"))
      (node (ref "KEY1") (pin "3") (pinfunction "P_3") (pintype "passive"))
      (node (ref "KEY1") (pin "4") (pinfunction "P1_4") (pintype "passive"))
      (node (ref "KEY2") (pin "3") (pinfunction "P_3") (pintype "passive"))
      (node (ref "KEY2") (pin "4") (pinfunction "P1_4") (pintype "passive"))
      (node (ref "KEY3") (pin "3") (pinfunction "P_3") (pintype "passive"))
      (node (ref "KEY3") (pin "4") (pinfunction "P1_4") (pintype "passive"))
      (node (ref "KEY4") (pin "3") (pinfunction "P_3") (pintype "passive"))
      (node (ref "KEY4") (pin "4") (pinfunction "P1_4") (pintype "passive"))
      (node (ref "KEY5") (pin "3") (pinfunction "P_3") (pintype "passive"))
      (node (ref "KEY5") (pin "4") (pinfunction "P1_4") (pintype "passive"))
      (node (ref "KEY6") (pin "3") (pinfunction "P_3") (pintype "passive"))
      (node (ref "KEY6") (pin "4") (pinfunction "P1_4") (pintype "passive"))
      (node (ref "KEY7") (pin "3") (pinfunction "P_3") (pintype "passive"))
      (node (ref "KEY7") (pin "4") (pinfunction "P1_4") (pintype "passive"))
      (node (ref "LA") (pin "3") (pinfunction "P_3") (pintype "passive"))
      (node (ref "LA") (pin "4") (pinfunction "P1_4") (pintype "passive"))
      (node (ref "LSR") (pin "3") (pinfunction "P_3") (pintype "passive"))
      (node (ref "LSR") (pin "4") (pinfunction "P1_4") (pintype "passive"))
      (node (ref "LXA") (pin "3") (pinfunction "P_3") (pintype "passive"))
      (node (ref "LXA") (pin "4") (pinfunction "P1_4") (pintype "passive"))
      (node (ref "RUN") (pin "3") (pinfunction "P_3") (pintype "passive"))
      (node (ref "RUN") (pin "4") (pinfunction "P1_4") (pintype "passive"))
    )
    (net (code "37") (name "INIT") (class "Default")
      (node (ref "E6") (pin "13") (pinfunction "3_13") (pintype "input"))
      (node (ref "INIT") (pin "1") (pinfunction "S_1") (pintype "passive"))
      (node (ref "INIT") (pin "2") (pinfunction "S1_2") (pintype "passive"))
      (node (ref "R8") (pin "1") (pinfunction "1_1") (pintype "passive"))
    )
    (net (code "38") (name "KEY0") (class "Default")
      (node (ref "E1") (pin "4") (pinfunction "7_4") (pintype "input"))
      (node (ref "KEY0") (pin "1") (pinfunction "S_1") (pintype "passive"))
      (node (ref "KEY0") (pin "2") (pinfunction "S1_2") (pintype "passive"))
      (node (ref "R18") (pin "1") (pinfunction "1_1") (pintype "passive"))
    )
    (net (code "39") (name "KEY1") (class "Default")
      (node (ref "E1") (pin "3") (pinfunction "6_3") (pintype "input"))
      (node (ref "KEY1") (pin "1") (pinfunction "S_1") (pintype "passive"))
      (node (ref "KEY1") (pin "2") (pinfunction "S1_2") (pintype "passive"))
      (node (ref "R17") (pin "1") (pinfunction "1_1") (pintype "passive"))
    )
    (net (code "40") (name "KEY2") (class "Default")
      (node (ref "E1") (pin "2") (pinfunction "5_2") (pintype "input"))
      (node (ref "KEY2") (pin "1") (pinfunction "S_1") (pintype "passive"))
      (node (ref "KEY2") (pin "2") (pinfunction "S1_2") (pintype "passive"))
      (node (ref "R16") (pin "1") (pinfunction "1_1") (pintype "passive"))
    )
    (net (code "41") (name "KEY3") (class "Default")
      (node (ref "E1") (pin "1") (pinfunction "4_1") (pintype "input"))
      (node (ref "KEY3") (pin "1") (pinfunction "S_1") (pintype "passive"))
      (node (ref "KEY3") (pin "2") (pinfunction "S1_2") (pintype "passive"))
      (node (ref "R15") (pin "1") (pinfunction "1_1") (pintype "passive"))
    )
    (net (code "42") (name "KEY4") (class "Default")
      (node (ref "E1") (pin "13") (pinfunction "3_13") (pintype "input"))
      (node (ref "KEY4") (pin "1") (pinfunction "S_1") (pintype "passive"))
      (node (ref "KEY4") (pin "2") (pinfunction "S1_2") (pintype "passive"))
      (node (ref "R14") (pin "1") (pinfunction "1_1") (pintype "passive"))
    )
    (net (code "43") (name "KEY5") (class "Default")
      (node (ref "E1") (pin "12") (pinfunction "2_12") (pintype "input"))
      (node (ref "KEY5") (pin "1") (pinfunction "S_1") (pintype "passive"))
      (node (ref "KEY5") (pin "2") (pinfunction "S1_2") (pintype "passive"))
      (node (ref "R13") (pin "1") (pinfunction "1_1") (pintype "passive"))
    )
    (net (code "44") (name "KEY6") (class "Default")
      (node (ref "E1") (pin "11") (pinfunction "1_11") (pintype "input"))
      (node (ref "KEY6") (pin "1") (pinfunction "S_1") (pintype "passive"))
      (node (ref "KEY6") (pin "2") (pinfunction "S1_2") (pintype "passive"))
      (node (ref "R12") (pin "1") (pinfunction "1_1") (pintype "passive"))
    )
    (net (code "45") (name "KEY7") (class "Default")
      (node (ref "E1") (pin "10") (pinfunction "0_10") (pintype "input"))
      (node (ref "KEY7") (pin "1") (pinfunction "S_1") (pintype "passive"))
      (node (ref "KEY7") (pin "2") (pinfunction "S1_2") (pintype "passive"))
      (node (ref "R11") (pin "1") (pinfunction "1_1") (pintype "passive"))
    )
    (net (code "46") (name "KEYSTB") (class "Default")
      (node (ref "E23") (pin "9") (pinfunction "Q_9") (pintype "output"))
      (node (ref "J2") (pin "2") (pinfunction "2_2") (pintype "passive"))
    )
    (net (code "47") (name "LA") (class "Default")
      (node (ref "E6") (pin "2") (pinfunction "5_2") (pintype "input"))
      (node (ref "LA") (pin "1") (pinfunction "S_1") (pintype "passive"))
      (node (ref "LA") (pin "2") (pinfunction "S1_2") (pintype "passive"))
      (node (ref "R6") (pin "1") (pinfunction "1_1") (pintype "passive"))
    )
    (net (code "48") (name "LSR") (class "Default")
      (node (ref "E6") (pin "3") (pinfunction "6_3") (pintype "input"))
      (node (ref "LSR") (pin "1") (pinfunction "S_1") (pintype "passive"))
      (node (ref "LSR") (pin "2") (pinfunction "S1_2") (pintype "passive"))
      (node (ref "R5") (pin "1") (pinfunction "1_1") (pintype "passive"))
    )
    (net (code "49") (name "LXA") (class "Default")
      (node (ref "E6") (pin "1") (pinfunction "4_1") (pintype "input"))
      (node (ref "LXA") (pin "1") (pinfunction "S_1") (pintype "passive"))
      (node (ref "LXA") (pin "2") (pinfunction "S1_2") (pintype "passive"))
      (node (ref "R7") (pin "1") (pinfunction "1_1") (pintype "passive"))
    )
    (net (code "50") (name "MCLOCK") (class "Default")
      (node (ref "E20") (pin "4") (pinfunction "O_4") (pintype "output"))
      (node (ref "E23") (pin "13") (pinfunction "CLR_13") (pintype "input"))
      (node (ref "E25") (pin "14") (pinfunction "CKA_14") (pintype "input"))
    )
    (net (code "51") (name "MPXA") (class "Default")
      (node (ref "E22") (pin "14") (pinfunction "B_14") (pintype "input"))
      (node (ref "E25") (pin "8") (pinfunction "QC_8") (pintype "output"))
      (node (ref "J2") (pin "14") (pinfunction "14_14") (pintype "passive"))
    )
    (net (code "52") (name "MPXB") (class "Default")
      (node (ref "E22") (pin "15") (pinfunction "A_15") (pintype "input"))
      (node (ref "E25") (pin "9") (pinfunction "QB_9") (pintype "output"))
      (node (ref "J2") (pin "13") (pinfunction "13_13") (pintype "passive"))
    )
    (net (code "53") (name "NUM") (class "Default")
      (node (ref "E20") (pin "10") (pinfunction "O_10") (pintype "output"))
      (node (ref "J2") (pin "11") (pinfunction "11_11") (pintype "passive"))
    )
    (net (code "54") (name "Net-(D1-C)") (class "Default")
      (node (ref "D1") (pin "K") (pinfunction "C_K") (pintype "passive"))
      (node (ref "E17") (pin "2") (pinfunction "1_2") (pintype "output"))
    )
    (net (code "55") (name "Net-(D1-PadA)") (class "Default")
      (node (ref "D1") (pin "A") (pinfunction "A_A") (pintype "passive"))
      (node (ref "R44") (pin "1") (pinfunction "1_1") (pintype "passive"))
    )
    (net (code "56") (name "Net-(D2-C)") (class "Default")
      (node (ref "D2") (pin "K") (pinfunction "C_K") (pintype "passive"))
      (node (ref "E17") (pin "5") (pinfunction "4_5") (pintype "output"))
    )
    (net (code "57") (name "Net-(D2-PadA)") (class "Default")
      (node (ref "D2") (pin "A") (pinfunction "A_A") (pintype "passive"))
      (node (ref "R41") (pin "1") (pinfunction "1_1") (pintype "passive"))
    )
    (net (code "58") (name "Net-(D3-C)") (class "Default")
      (node (ref "D3") (pin "K") (pinfunction "C_K") (pintype "passive"))
      (node (ref "E17") (pin "7") (pinfunction "6_7") (pintype "output"))
    )
    (net (code "59") (name "Net-(D3-PadA)") (class "Default")
      (node (ref "D3") (pin "A") (pinfunction "A_A") (pintype "passive"))
      (node (ref "R39") (pin "1") (pinfunction "1_1") (pintype "passive"))
    )
    (net (code "60") (name "Net-(D4-C)") (class "Default")
      (node (ref "D4") (pin "K") (pinfunction "C_K") (pintype "passive"))
      (node (ref "E17") (pin "1") (pinfunction "0_1") (pintype "output"))
    )
    (net (code "61") (name "Net-(D4-PadA)") (class "Default")
      (node (ref "D4") (pin "A") (pinfunction "A_A") (pintype "passive"))
      (node (ref "R45") (pin "1") (pinfunction "1_1") (pintype "passive"))
    )
    (net (code "62") (name "Net-(D5-C)") (class "Default")
      (node (ref "D5") (pin "K") (pinfunction "C_K") (pintype "passive"))
      (node (ref "E17") (pin "4") (pinfunction "3_4") (pintype "output"))
    )
    (net (code "63") (name "Net-(D5-PadA)") (class "Default")
      (node (ref "D5") (pin "A") (pinfunction "A_A") (pintype "passive"))
      (node (ref "R42") (pin "1") (pinfunction "1_1") (pintype "passive"))
    )
    (net (code "64") (name "Net-(D6-C)") (class "Default")
      (node (ref "D6") (pin "K") (pinfunction "C_K") (pintype "passive"))
      (node (ref "E17") (pin "6") (pinfunction "5_6") (pintype "output"))
    )
    (net (code "65") (name "Net-(D6-PadA)") (class "Default")
      (node (ref "D6") (pin "A") (pinfunction "A_A") (pintype "passive"))
      (node (ref "R40") (pin "1") (pinfunction "1_1") (pintype "passive"))
    )
    (net (code "66") (name "Net-(D7-C)") (class "Default")
      (node (ref "D7") (pin "K") (pinfunction "C_K") (pintype "passive"))
      (node (ref "E17") (pin "3") (pinfunction "2_3") (pintype "output"))
    )
    (net (code "67") (name "Net-(D7-PadA)") (class "Default")
      (node (ref "D7") (pin "A") (pinfunction "A_A") (pintype "passive"))
      (node (ref "R43") (pin "1") (pinfunction "1_1") (pintype "passive"))
    )
    (net (code "68") (name "Net-(D8-C)") (class "Default")
      (node (ref "D8") (pin "K") (pinfunction "C_K") (pintype "passive"))
      (node (ref "E19") (pin "2") (pinfunction "O_2") (pintype "open_collector"))
    )
    (net (code "69") (name "Net-(D8-PadA)") (class "Default")
      (node (ref "D8") (pin "A") (pinfunction "A_A") (pintype "passive"))
      (node (ref "R46") (pin "1") (pinfunction "1_1") (pintype "passive"))
    )
    (net (code "70") (name "Net-(E1A-EO)") (class "Default")
      (node (ref "E1") (pin "15") (pinfunction "EO_15") (pintype "output"))
      (node (ref "E6") (pin "5") (pinfunction "EI_5") (pintype "input"))
    )
    (net (code "71") (name "Net-(E1A-GS)") (class "Default")
      (node (ref "E1") (pin "14") (pinfunction "GS_14") (pintype "output"))
      (node (ref "E20") (pin "11") (pinfunction "I_11") (pintype "input"))
      (node (ref "E21") (pin "9") (pinfunction "I0_9") (pintype "input"))
    )
    (net (code "72") (name "Net-(E2A-O)") (class "Default")
      (node (ref "E2") (pin "3") (pinfunction "O_3") (pintype "output"))
      (node (ref "E6") (pin "12") (pinfunction "2_12") (pintype "input"))
    )
    (net (code "73") (name "Net-(E2C-O)") (class "Default")
      (node (ref "E2") (pin "8") (pinfunction "O_8") (pintype "output"))
      (node (ref "E6") (pin "10") (pinfunction "0_10") (pintype "input"))
    )
    (net (code "74") (name "Net-(E2D-O)") (class "Default")
      (node (ref "E2") (pin "11") (pinfunction "O_11") (pintype "output"))
      (node (ref "E6") (pin "11") (pinfunction "1_11") (pintype "input"))
    )
    (net (code "75") (name "Net-(E10A-I0)") (class "Default")
      (node (ref "E10") (pin "1") (pinfunction "I0_1") (pintype "input"))
      (node (ref "E18") (pin "12") (pinfunction "~{Q}_12") (pintype "output"))
    )
    (net (code "76") (name "Net-(E10B-I0)") (class "Default")
      (node (ref "E1") (pin "9") (pinfunction "A0_9") (pintype "output"))
      (node (ref "E10") (pin "4") (pinfunction "I0_4") (pintype "input"))
    )
    (net (code "77") (name "Net-(E10B-I1)") (class "Default")
      (node (ref "E10") (pin "5") (pinfunction "I1_5") (pintype "input"))
      (node (ref "E6") (pin "9") (pinfunction "A0_9") (pintype "output"))
    )
    (net (code "78") (name "Net-(E10C-I0)") (class "Default")
      (node (ref "E10") (pin "9") (pinfunction "I0_9") (pintype "input"))
      (node (ref "E6") (pin "7") (pinfunction "A1_7") (pintype "output"))
    )
    (net (code "79") (name "Net-(E10C-I1)") (class "Default")
      (node (ref "E1") (pin "7") (pinfunction "A1_7") (pintype "output"))
      (node (ref "E10") (pin "10") (pinfunction "I1_10") (pintype "input"))
    )
    (net (code "80") (name "Net-(E10D-I0)") (class "Default")
      (node (ref "E10") (pin "12") (pinfunction "I0_12") (pintype "input"))
      (node (ref "E6") (pin "6") (pinfunction "A2_6") (pintype "output"))
    )
    (net (code "81") (name "Net-(E10D-I1)") (class "Default")
      (node (ref "E1") (pin "6") (pinfunction "A2_6") (pintype "output"))
      (node (ref "E10") (pin "13") (pinfunction "I1_13") (pintype "input"))
    )
    (net (code "82") (name "Net-(E15-A)") (class "Default")
      (node (ref "E15") (pin "7") (pinfunction "A_7") (pintype "passive"))
      (node (ref "E16") (pin "13") (pinfunction "A_13") (pintype "open_collector"))
    )
    (net (code "83") (name "Net-(E15-B)") (class "Default")
      (node (ref "E15") (pin "6") (pinfunction "B_6") (pintype "passive"))
      (node (ref "E16") (pin "12") (pinfunction "B_12") (pintype "open_collector"))
    )
    (net (code "84") (name "Net-(E15-C)") (class "Default")
      (node (ref "E15") (pin "4") (pinfunction "C_4") (pintype "passive"))
      (node (ref "E16") (pin "11") (pinfunction "C_11") (pintype "open_collector"))
    )
    (net (code "85") (name "Net-(E15-D)") (class "Default")
      (node (ref "E15") (pin "2") (pinfunction "D_2") (pintype "passive"))
      (node (ref "E16") (pin "10") (pinfunction "D_10") (pintype "open_collector"))
    )
    (net (code "86") (name "Net-(E15-E)") (class "Default")
      (node (ref "E15") (pin "1") (pinfunction "E_1") (pintype "passive"))
      (node (ref "E16") (pin "9") (pinfunction "E_9") (pintype "open_collector"))
    )
    (net (code "87") (name "Net-(E15-F)") (class "Default")
      (node (ref "E15") (pin "9") (pinfunction "F_9") (pintype "passive"))
      (node (ref "E16") (pin "15") (pinfunction "F_15") (pintype "open_collector"))
    )
    (net (code "88") (name "Net-(E15-G)") (class "Default")
      (node (ref "E15") (pin "10") (pinfunction "G_10") (pintype "passive"))
      (node (ref "E16") (pin "14") (pinfunction "G_14") (pintype "open_collector"))
    )
    (net (code "89") (name "Net-(E18A-A)") (class "Default")
      (node (ref "E18") (pin "1") (pinfunction "A_1") (pintype "input"))
      (node (ref "E18") (pin "5") (pinfunction "Q_5") (pintype "output"))
    )
    (net (code "90") (name "Net-(E18A-C)") (class "Default")
      (node (ref "C17") (pin "-") (pinfunction "-_-") (pintype "passive"))
      (node (ref "E18") (pin "14") (pinfunction "C_14") (pintype "input"))
    )
    (net (code "91") (name "Net-(E18A-R{slash}C)") (class "Default")
      (node (ref "C17") (pin "+") (pinfunction "+_+") (pintype "passive"))
      (node (ref "E18") (pin "15") (pinfunction "R/C_15") (pintype "input"))
      (node (ref "R2") (pin "2") (pinfunction "2_2") (pintype "passive"))
    )
    (net (code "92") (name "Net-(E18A-~{Q})") (class "Default")
      (node (ref "E18") (pin "10") (pinfunction "B_10") (pintype "input"))
      (node (ref "E18") (pin "4") (pinfunction "~{Q}_4") (pintype "output"))
    )
    (net (code "93") (name "Net-(E18B-C)") (class "Default")
      (node (ref "C18") (pin "2") (pinfunction "2_2") (pintype "passive"))
      (node (ref "C21") (pin "2") (pinfunction "2_2") (pintype "passive"))
      (node (ref "E18") (pin "6") (pinfunction "C_6") (pintype "input"))
    )
    (net (code "94") (name "Net-(E18B-R{slash}C)") (class "Default")
      (node (ref "C18") (pin "1") (pinfunction "1_1") (pintype "passive"))
      (node (ref "C21") (pin "1") (pinfunction "1_1") (pintype "passive"))
      (node (ref "E18") (pin "7") (pinfunction "R/C_7") (pintype "input"))
      (node (ref "R1") (pin "1") (pinfunction "1_1") (pintype "passive"))
    )
    (net (code "95") (name "Net-(E19B-I)") (class "Default")
      (node (ref "E19") (pin "3") (pinfunction "I_3") (pintype "input"))
      (node (ref "E22") (pin "4") (pinfunction "O3_4") (pintype "output"))
    )
    (net (code "96") (name "Net-(E19B-O)") (class "Default")
      (node (ref "E19") (pin "4") (pinfunction "O_4") (pintype "open_collector"))
      (node (ref "R27") (pin "1") (pinfunction "1_1") (pintype "passive"))
      (node (ref "R34") (pin "2") (pinfunction "2_2") (pintype "passive"))
    )
    (net (code "97") (name "Net-(E19C-I)") (class "Default")
      (node (ref "E19") (pin "5") (pinfunction "I_5") (pintype "input"))
      (node (ref "E22") (pin "5") (pinfunction "O4_5") (pintype "output"))
    )
    (net (code "98") (name "Net-(E19C-O)") (class "Default")
      (node (ref "E19") (pin "6") (pinfunction "O_6") (pintype "open_collector"))
      (node (ref "R28") (pin "1") (pinfunction "1_1") (pintype "passive"))
      (node (ref "R38") (pin "1") (pinfunction "1_1") (pintype "passive"))
    )
    (net (code "99") (name "Net-(E19D-I)") (class "Default")
      (node (ref "E19") (pin "9") (pinfunction "I_9") (pintype "input"))
      (node (ref "E22") (pin "3") (pinfunction "O2_3") (pintype "output"))
    )
    (net (code "100") (name "Net-(E19D-O)") (class "Default")
      (node (ref "E19") (pin "8") (pinfunction "O_8") (pintype "open_collector"))
      (node (ref "R26") (pin "1") (pinfunction "1_1") (pintype "passive"))
      (node (ref "R35") (pin "2") (pinfunction "2_2") (pintype "passive"))
    )
    (net (code "101") (name "Net-(E19E-I)") (class "Default")
      (node (ref "E19") (pin "11") (pinfunction "I_11") (pintype "input"))
      (node (ref "E22") (pin "2") (pinfunction "O1_2") (pintype "output"))
    )
    (net (code "102") (name "Net-(E19E-O)") (class "Default")
      (node (ref "E19") (pin "10") (pinfunction "O_10") (pintype "open_collector"))
      (node (ref "R25") (pin "1") (pinfunction "1_1") (pintype "passive"))
      (node (ref "R36") (pin "2") (pinfunction "2_2") (pintype "passive"))
    )
    (net (code "103") (name "Net-(E19F-I)") (class "Default")
      (node (ref "E19") (pin "13") (pinfunction "I_13") (pintype "input"))
      (node (ref "E22") (pin "1") (pinfunction "O0_1") (pintype "output"))
    )
    (net (code "104") (name "Net-(E19F-O)") (class "Default")
      (node (ref "E19") (pin "12") (pinfunction "O_12") (pintype "open_collector"))
      (node (ref "R24") (pin "1") (pinfunction "1_1") (pintype "passive"))
      (node (ref "R37") (pin "2") (pinfunction "2_2") (pintype "passive"))
    )
    (net (code "105") (name "Net-(E20A-I)") (class "Default")
      (node (ref "E20") (pin "1") (pinfunction "I_1") (pintype "input"))
      (node (ref "E21") (pin "5") (pinfunction "I3_5") (pintype "input"))
      (node (ref "E24") (pin "10") (pinfunction "QD_10") (pintype "output"))
    )
    (net (code "106") (name "Net-(E20A-O)") (class "Default")
      (node (ref "E20") (pin "2") (pinfunction "O_2") (pintype "output"))
      (node (ref "E23") (pin "3") (pinfunction "CLK_3") (pintype "input"))
    )
    (net (code "107") (name "Net-(E20F-I)") (class "Default")
      (node (ref "E20") (pin "13") (pinfunction "I_13") (pintype "input"))
      (node (ref "E21") (pin "8") (pinfunction "O_8") (pintype "output"))
      (node (ref "E23") (pin "2") (pinfunction "D_2") (pintype "input"))
    )
    (net (code "108") (name "Net-(E20F-O)") (class "Default")
      (node (ref "E20") (pin "12") (pinfunction "O_12") (pintype "output"))
      (node (ref "E24") (pin "1") (pinfunction "SER_1") (pintype "input"))
    )
    (net (code "109") (name "Net-(E21A-I0)") (class "Default")
      (node (ref "E21") (pin "1") (pinfunction "I0_1") (pintype "input"))
      (node (ref "E24") (pin "13") (pinfunction "QA_13") (pintype "output"))
    )
    (net (code "110") (name "Net-(E21A-I1)") (class "Default")
      (node (ref "E21") (pin "2") (pinfunction "I1_2") (pintype "input"))
      (node (ref "E24") (pin "12") (pinfunction "QB_12") (pintype "output"))
    )
    (net (code "111") (name "Net-(E21A-I2)") (class "Default")
      (node (ref "E21") (pin "4") (pinfunction "I2_4") (pintype "input"))
      (node (ref "E24") (pin "11") (pinfunction "QC_11") (pintype "output"))
    )
    (net (code "112") (name "Net-(E21A-O)") (class "Default")
      (node (ref "E21") (pin "6") (pinfunction "O_6") (pintype "output"))
      (node (ref "E23") (pin "1") (pinfunction "CLR_1") (pintype "input"))
    )
    (net (code "113") (name "Net-(E22A-C)") (class "Default")
      (node (ref "E22") (pin "13") (pinfunction "C_13") (pintype "input"))
      (node (ref "E25") (pin "11") (pinfunction "QD_11") (pintype "output"))
    )
    (net (code "114") (name "Net-(E23A-Q)") (class "Default")
      (node (ref "E23") (pin "11") (pinfunction "CLK_11") (pintype "input"))
      (node (ref "E23") (pin "5") (pinfunction "Q_5") (pintype "output"))
    )
    (net (code "115") (name "Net-(E25A-CKB)") (class "Default")
      (node (ref "E25") (pin "1") (pinfunction "CKB_1") (pintype "input"))
      (node (ref "E25") (pin "12") (pinfunction "QA_12") (pintype "output"))
    )
    (net (code "116") (name "Net-(Q1-B)") (class "Default")
      (node (ref "Q1") (pin "2") (pinfunction "B_2") (pintype "passive"))
      (node (ref "R38") (pin "2") (pinfunction "2_2") (pintype "passive"))
    )
    (net (code "117") (name "Net-(Q1-C)") (class "Default")
      (node (ref "Q1") (pin "3") (pinfunction "C_3") (pintype "passive"))
      (node (ref "R33") (pin "1") (pinfunction "1_1") (pintype "passive"))
    )
    (net (code "118") (name "Net-(Q1-E)") (class "Default")
      (node (ref "E15") (pin "3") (pinfunction "CA_3") (pintype "passive"))
      (node (ref "E15") (pin "8") (pinfunction "CA_8") (pintype "passive"))
      (node (ref "Q1") (pin "1") (pinfunction "E_1") (pintype "passive"))
    )
    (net (code "119") (name "Net-(Q2-B)") (class "Default")
      (node (ref "Q2") (pin "2") (pinfunction "B_2") (pintype "passive"))
      (node (ref "R37") (pin "1") (pinfunction "1_1") (pintype "passive"))
    )
    (net (code "120") (name "Net-(Q2-C)") (class "Default")
      (node (ref "Q2") (pin "3") (pinfunction "C_3") (pintype "passive"))
      (node (ref "R29") (pin "1") (pinfunction "1_1") (pintype "passive"))
    )
    (net (code "121") (name "Net-(Q2-E)") (class "Default")
      (node (ref "E3") (pin "3") (pinfunction "CA_3") (pintype "passive"))
      (node (ref "E3") (pin "8") (pinfunction "CA_8") (pintype "passive"))
      (node (ref "E9") (pin "3") (pinfunction "CA_3") (pintype "passive"))
      (node (ref "E9") (pin "8") (pinfunction "CA_8") (pintype "passive"))
      (node (ref "Q2") (pin "1") (pinfunction "E_1") (pintype "passive"))
    )
    (net (code "122") (name "Net-(Q3-B)") (class "Default")
      (node (ref "Q3") (pin "2") (pinfunction "B_2") (pintype "passive"))
      (node (ref "R36") (pin "1") (pinfunction "1_1") (pintype "passive"))
    )
    (net (code "123") (name "Net-(Q3-C)") (class "Default")
      (node (ref "Q3") (pin "3") (pinfunction "C_3") (pintype "passive"))
      (node (ref "R30") (pin "1") (pinfunction "1_1") (pintype "passive"))
    )
    (net (code "124") (name "Net-(Q3-E)") (class "Default")
      (node (ref "E11") (pin "3") (pinfunction "CA_3") (pintype "passive"))
      (node (ref "E11") (pin "8") (pinfunction "CA_8") (pintype "passive"))
      (node (ref "E4") (pin "3") (pinfunction "CA_3") (pintype "passive"))
      (node (ref "E4") (pin "8") (pinfunction "CA_8") (pintype "passive"))
      (node (ref "Q3") (pin "1") (pinfunction "E_1") (pintype "passive"))
    )
    (net (code "125") (name "Net-(Q4-B)") (class "Default")
      (node (ref "Q4") (pin "2") (pinfunction "B_2") (pintype "passive"))
      (node (ref "R35") (pin "1") (pinfunction "1_1") (pintype "passive"))
    )
    (net (code "126") (name "Net-(Q4-C)") (class "Default")
      (node (ref "Q4") (pin "3") (pinfunction "C_3") (pintype "passive"))
      (node (ref "R31") (pin "1") (pinfunction "1_1") (pintype "passive"))
    )
    (net (code "127") (name "Net-(Q4-E)") (class "Default")
      (node (ref "E12") (pin "3") (pinfunction "CA_3") (pintype "passive"))
      (node (ref "E12") (pin "8") (pinfunction "CA_8") (pintype "passive"))
      (node (ref "E5") (pin "3") (pinfunction "CA_3") (pintype "passive"))
      (node (ref "E5") (pin "8") (pinfunction "CA_8") (pintype "passive"))
      (node (ref "Q4") (pin "1") (pinfunction "E_1") (pintype "passive"))
    )
    (net (code "128") (name "Net-(Q5-B)") (class "Default")
      (node (ref "Q5") (pin "2") (pinfunction "B_2") (pintype "passive"))
      (node (ref "R34") (pin "1") (pinfunction "1_1") (pintype "passive"))
    )
    (net (code "129") (name "Net-(Q5-C)") (class "Default")
      (node (ref "Q5") (pin "3") (pinfunction "C_3") (pintype "passive"))
      (node (ref "R32") (pin "1") (pinfunction "1_1") (pintype "passive"))
    )
    (net (code "130") (name "Net-(Q5-E)") (class "Default")
      (node (ref "E14") (pin "3") (pinfunction "CA_3") (pintype "passive"))
      (node (ref "E14") (pin "8") (pinfunction "CA_8") (pintype "passive"))
      (node (ref "E7") (pin "3") (pinfunction "CA_3") (pintype "passive"))
      (node (ref "E7") (pin "8") (pinfunction "CA_8") (pintype "passive"))
      (node (ref "Q5") (pin "1") (pinfunction "E_1") (pintype "passive"))
    )
    (net (code "131") (name "RUN") (class "Default")
      (node (ref "E2") (pin "2") (pinfunction "I1_2") (pintype "input"))
      (node (ref "R9") (pin "1") (pinfunction "1_1") (pintype "passive"))
      (node (ref "RUN") (pin "1") (pinfunction "S_1") (pintype "passive"))
      (node (ref "RUN") (pin "2") (pinfunction "S1_2") (pintype "passive"))
    )
    (net (code "132") (name "VCC") (class "Default")
      (node (ref "C1") (pin "1") (pinfunction "1_1") (pintype "passive"))
      (node (ref "C10") (pin "1") (pinfunction "1_1") (pintype "passive"))
      (node (ref "C11") (pin "1") (pinfunction "1_1") (pintype "passive"))
      (node (ref "C12") (pin "1") (pinfunction "1_1") (pintype "passive"))
      (node (ref "C13") (pin "1") (pinfunction "1_1") (pintype "passive"))
      (node (ref "C14") (pin "1") (pinfunction "1_1") (pintype "passive"))
      (node (ref "C15") (pin "1") (pinfunction "1_1") (pintype "passive"))
      (node (ref "C16") (pin "1") (pinfunction "1_1") (pintype "passive"))
      (node (ref "C19") (pin "+") (pinfunction "+_+") (pintype "passive"))
      (node (ref "C2") (pin "1") (pinfunction "1_1") (pintype "passive"))
      (node (ref "C20") (pin "+") (pinfunction "+_+") (pintype "passive"))
      (node (ref "C3") (pin "1") (pinfunction "1_1") (pintype "passive"))
      (node (ref "C4") (pin "1") (pinfunction "1_1") (pintype "passive"))
      (node (ref "C5") (pin "1") (pinfunction "1_1") (pintype "passive"))
      (node (ref "C6") (pin "1") (pinfunction "1_1") (pintype "passive"))
      (node (ref "C7") (pin "1") (pinfunction "1_1") (pintype "passive"))
      (node (ref "C8") (pin "1") (pinfunction "1_1") (pintype "passive"))
      (node (ref "C9") (pin "1") (pinfunction "1_1") (pintype "passive"))
      (node (ref "E13") (pin "3") (pinfunction "LT_3") (pintype "input"))
      (node (ref "E13") (pin "4") (pinfunction "BI/RBO_4") (pintype "input"))
      (node (ref "E13") (pin "5") (pinfunction "RBI_5") (pintype "input"))
      (node (ref "E16") (pin "3") (pinfunction "LT_3") (pintype "input"))
      (node (ref "E16") (pin "4") (pinfunction "BI/RBO_4") (pintype "input"))
      (node (ref "E16") (pin "5") (pinfunction "RBI_5") (pintype "input"))
      (node (ref "E18") (pin "3") (pinfunction "CLR_3") (pintype "input"))
      (node (ref "E23") (pin "10") (pinfunction "PRE_10") (pintype "input"))
      (node (ref "E23") (pin "12") (pinfunction "D_12") (pintype "input"))
      (node (ref "E23") (pin "4") (pinfunction "PRE_4") (pintype "input"))
      (node (ref "E24") (pin "2") (pinfunction "A_2") (pintype "input"))
      (node (ref "E24") (pin "3") (pinfunction "B_3") (pintype "input"))
      (node (ref "E24") (pin "4") (pinfunction "C_4") (pintype "input"))
      (node (ref "E24") (pin "5") (pinfunction "D_5") (pintype "input"))
      (node (ref "E24") (pin "8") (pinfunction "CK2_8") (pintype "input"))
      (node (ref "E8") (pin "3") (pinfunction "LT_3") (pintype "input"))
      (node (ref "E8") (pin "4") (pinfunction "BI/RBO_4") (pintype "input"))
      (node (ref "E8") (pin "5") (pinfunction "RBI_5") (pintype "input"))
      (node (ref "J1") (pin "16") (pinfunction "16_16") (pintype "passive"))
      (node (ref "J2") (pin "16") (pinfunction "16_16") (pintype "passive"))
      (node (ref "R1") (pin "2") (pinfunction "2_2") (pintype "passive"))
      (node (ref "R10") (pin "2") (pinfunction "2_2") (pintype "passive"))
      (node (ref "R11") (pin "2") (pinfunction "2_2") (pintype "passive"))
      (node (ref "R12") (pin "2") (pinfunction "2_2") (pintype "passive"))
      (node (ref "R13") (pin "2") (pinfunction "2_2") (pintype "passive"))
      (node (ref "R14") (pin "2") (pinfunction "2_2") (pintype "passive"))
      (node (ref "R15") (pin "2") (pinfunction "2_2") (pintype "passive"))
      (node (ref "R16") (pin "2") (pinfunction "2_2") (pintype "passive"))
      (node (ref "R17") (pin "2") (pinfunction "2_2") (pintype "passive"))
      (node (ref "R18") (pin "2") (pinfunction "2_2") (pintype "passive"))
      (node (ref "R19") (pin "2") (pinfunction "2_2") (pintype "passive"))
      (node (ref "R2") (pin "1") (pinfunction "1_1") (pintype "passive"))
      (node (ref "R20") (pin "2") (pinfunction "2_2") (pintype "passive"))
      (node (ref "R21") (pin "2") (pinfunction "2_2") (pintype "passive"))
      (node (ref "R22") (pin "2") (pinfunction "2_2") (pintype "passive"))
      (node (ref "R23") (pin "2") (pinfunction "2_2") (pintype "passive"))
      (node (ref "R24") (pin "2") (pinfunction "2_2") (pintype "passive"))
      (node (ref "R25") (pin "2") (pinfunction "2_2") (pintype "passive"))
      (node (ref "R26") (pin "2") (pinfunction "2_2") (pintype "passive"))
      (node (ref "R27") (pin "2") (pinfunction "2_2") (pintype "passive"))
      (node (ref "R28") (pin "2") (pinfunction "2_2") (pintype "passive"))
      (node (ref "R29") (pin "2") (pinfunction "2_2") (pintype "passive"))
      (node (ref "R3") (pin "2") (pinfunction "2_2") (pintype "passive"))
      (node (ref "R30") (pin "2") (pinfunction "2_2") (pintype "passive"))
      (node (ref "R31") (pin "2") (pinfunction "2_2") (pintype "passive"))
      (node (ref "R32") (pin "2") (pinfunction "2_2") (pintype "passive"))
      (node (ref "R33") (pin "2") (pinfunction "2_2") (pintype "passive"))
      (node (ref "R39") (pin "2") (pinfunction "2_2") (pintype "passive"))
      (node (ref "R4") (pin "1") (pinfunction "1_1") (pintype "passive"))
      (node (ref "R40") (pin "2") (pinfunction "2_2") (pintype "passive"))
      (node (ref "R41") (pin "2") (pinfunction "2_2") (pintype "passive"))
      (node (ref "R42") (pin "2") (pinfunction "2_2") (pintype "passive"))
      (node (ref "R43") (pin "2") (pinfunction "2_2") (pintype "passive"))
      (node (ref "R44") (pin "2") (pinfunction "2_2") (pintype "passive"))
      (node (ref "R45") (pin "2") (pinfunction "2_2") (pintype "passive"))
      (node (ref "R46") (pin "2") (pinfunction "2_2") (pintype "passive"))
      (node (ref "R5") (pin "2") (pinfunction "2_2") (pintype "passive"))
      (node (ref "R6") (pin "2") (pinfunction "2_2") (pintype "passive"))
      (node (ref "R7") (pin "2") (pinfunction "2_2") (pintype "passive"))
      (node (ref "R8") (pin "2") (pinfunction "2_2") (pintype "passive"))
      (node (ref "R9") (pin "2") (pinfunction "2_2") (pintype "passive"))
      (node (ref "VCC") (pin "1") (pinfunction "P_1") (pintype "passive"))
    )
    (net (code "133") (name "unconnected-(E3-DP-Pad5)") (class "Default")
      (node (ref "E3") (pin "5") (pinfunction "DP_5") (pintype "passive"))
    )
    (net (code "134") (name "unconnected-(E4-DP-Pad5)") (class "Default")
      (node (ref "E4") (pin "5") (pinfunction "DP_5") (pintype "passive"))
    )
    (net (code "135") (name "unconnected-(E5-DP-Pad5)") (class "Default")
      (node (ref "E5") (pin "5") (pinfunction "DP_5") (pintype "passive"))
    )
    (net (code "136") (name "unconnected-(E6A-EO-Pad15)") (class "Default")
      (node (ref "E6") (pin "15") (pinfunction "EO_15") (pintype "output"))
    )
    (net (code "137") (name "unconnected-(E7-DP-Pad5)") (class "Default")
      (node (ref "E7") (pin "5") (pinfunction "DP_5") (pintype "passive"))
    )
    (net (code "138") (name "unconnected-(E9-DP-Pad5)") (class "Default")
      (node (ref "E9") (pin "5") (pinfunction "DP_5") (pintype "passive"))
    )
    (net (code "139") (name "unconnected-(E11-DP-Pad5)") (class "Default")
      (node (ref "E11") (pin "5") (pinfunction "DP_5") (pintype "passive"))
    )
    (net (code "140") (name "unconnected-(E12-DP-Pad5)") (class "Default")
      (node (ref "E12") (pin "5") (pinfunction "DP_5") (pintype "passive"))
    )
    (net (code "141") (name "unconnected-(E14-DP-Pad5)") (class "Default")
      (node (ref "E14") (pin "5") (pinfunction "DP_5") (pintype "passive"))
    )
    (net (code "142") (name "unconnected-(E15-DP-Pad5)") (class "Default")
      (node (ref "E15") (pin "5") (pinfunction "DP_5") (pintype "passive"))
    )
    (net (code "143") (name "unconnected-(E17A-7-Pad9)") (class "Default")
      (node (ref "E17") (pin "9") (pinfunction "7_9") (pintype "output"))
    )
    (net (code "144") (name "unconnected-(E17A-8-Pad10)") (class "Default")
      (node (ref "E17") (pin "10") (pinfunction "8_10") (pintype "output"))
    )
    (net (code "145") (name "unconnected-(E17A-9-Pad11)") (class "Default")
      (node (ref "E17") (pin "11") (pinfunction "9_11") (pintype "output"))
    )
    (net (code "146") (name "unconnected-(E18A-Q-Pad13)") (class "Default")
      (node (ref "E18") (pin "13") (pinfunction "Q_13") (pintype "output"))
    )
    (net (code "147") (name "unconnected-(E22A-O5-Pad6)") (class "Default")
      (node (ref "E22") (pin "6") (pinfunction "O5_6") (pintype "output"))
    )
    (net (code "148") (name "unconnected-(E22A-O6-Pad7)") (class "Default")
      (node (ref "E22") (pin "7") (pinfunction "O6_7") (pintype "output"))
    )
    (net (code "149") (name "unconnected-(E22A-O7-Pad9)") (class "Default")
      (node (ref "E22") (pin "9") (pinfunction "O7_9") (pintype "output"))
    )
    (net (code "150") (name "unconnected-(E22A-O8-Pad10)") (class "Default")
      (node (ref "E22") (pin "10") (pinfunction "O8_10") (pintype "output"))
    )
    (net (code "151") (name "unconnected-(E22A-O9-Pad11)") (class "Default")
      (node (ref "E22") (pin "11") (pinfunction "O9_11") (pintype "output"))
    )
    (net (code "152") (name "unconnected-(E23B-~{Q}-Pad8)") (class "Default")
      (node (ref "E23") (pin "8") (pinfunction "~{Q}_8") (pintype "output"))
    )
    (net (code "153") (name "~{EXTPUL}") (class "Default")
      (node (ref "E10") (pin "2") (pinfunction "I1_2") (pintype "input"))
      (node (ref "J2") (pin "9") (pinfunction "9_9") (pintype "passive"))
      (node (ref "R4") (pin "2") (pinfunction "2_2") (pintype "passive"))
    )
    (net (code "154") (name "~{FUN}") (class "Default")
      (node (ref "E21") (pin "12") (pinfunction "I2_12") (pintype "input"))
      (node (ref "E21") (pin "13") (pinfunction "I3_13") (pintype "input"))
      (node (ref "E6") (pin "14") (pinfunction "GS_14") (pintype "output"))
      (node (ref "J2") (pin "15") (pinfunction "15_15") (pintype "passive"))
    )
    (net (code "155") (name "~{KEY-F}") (class "Default")
      (node (ref "E23") (pin "6") (pinfunction "~{Q}_6") (pintype "output"))
      (node (ref "J2") (pin "3") (pinfunction "3_3") (pintype "passive"))
    )
    (net (code "156") (name "~{KFUN0}") (class "Default")
      (node (ref "E10") (pin "11") (pinfunction "O_11") (pintype "output"))
      (node (ref "J1") (pin "3") (pinfunction "3_3") (pintype "passive"))
    )
    (net (code "157") (name "~{KFUN1}") (class "Default")
      (node (ref "E10") (pin "8") (pinfunction "O_8") (pintype "output"))
      (node (ref "J1") (pin "2") (pinfunction "2_2") (pintype "passive"))
    )
    (net (code "158") (name "~{KFUN2}") (class "Default")
      (node (ref "E10") (pin "6") (pinfunction "O_6") (pintype "output"))
      (node (ref "J1") (pin "1") (pinfunction "1_1") (pintype "passive"))
    )
    (net (code "159") (name "~{MCLOCK}") (class "Default")
      (node (ref "E10") (pin "3") (pinfunction "O_3") (pintype "output"))
      (node (ref "E20") (pin "3") (pinfunction "I_3") (pintype "input"))
      (node (ref "E24") (pin "9") (pinfunction "CK1_9") (pintype "input"))
      (node (ref "J2") (pin "1") (pinfunction "1_1") (pintype "passive"))
    )
    (net (code "160") (name "~{SHLT}") (class "Default")
      (node (ref "!SHLT") (pin "1") (pinfunction "S_1") (pintype "passive"))
      (node (ref "!SHLT") (pin "2") (pinfunction "S1_2") (pintype "passive"))
      (node (ref "E2") (pin "1") (pinfunction "I0_1") (pintype "input"))
      (node (ref "J1") (pin "5") (pinfunction "5_5") (pintype "passive"))
      (node (ref "R19") (pin "1") (pinfunction "1_1") (pintype "passive"))
    )
    (net (code "161") (name "~{STHIS}") (class "Default")
      (node (ref "E2") (pin "6") (pinfunction "O_6") (pintype "output"))
      (node (ref "J1") (pin "4") (pinfunction "4_4") (pintype "passive"))
    )
  )
)
